# untitled.net
KiCad netlist of a schematic drawn in EAGLE
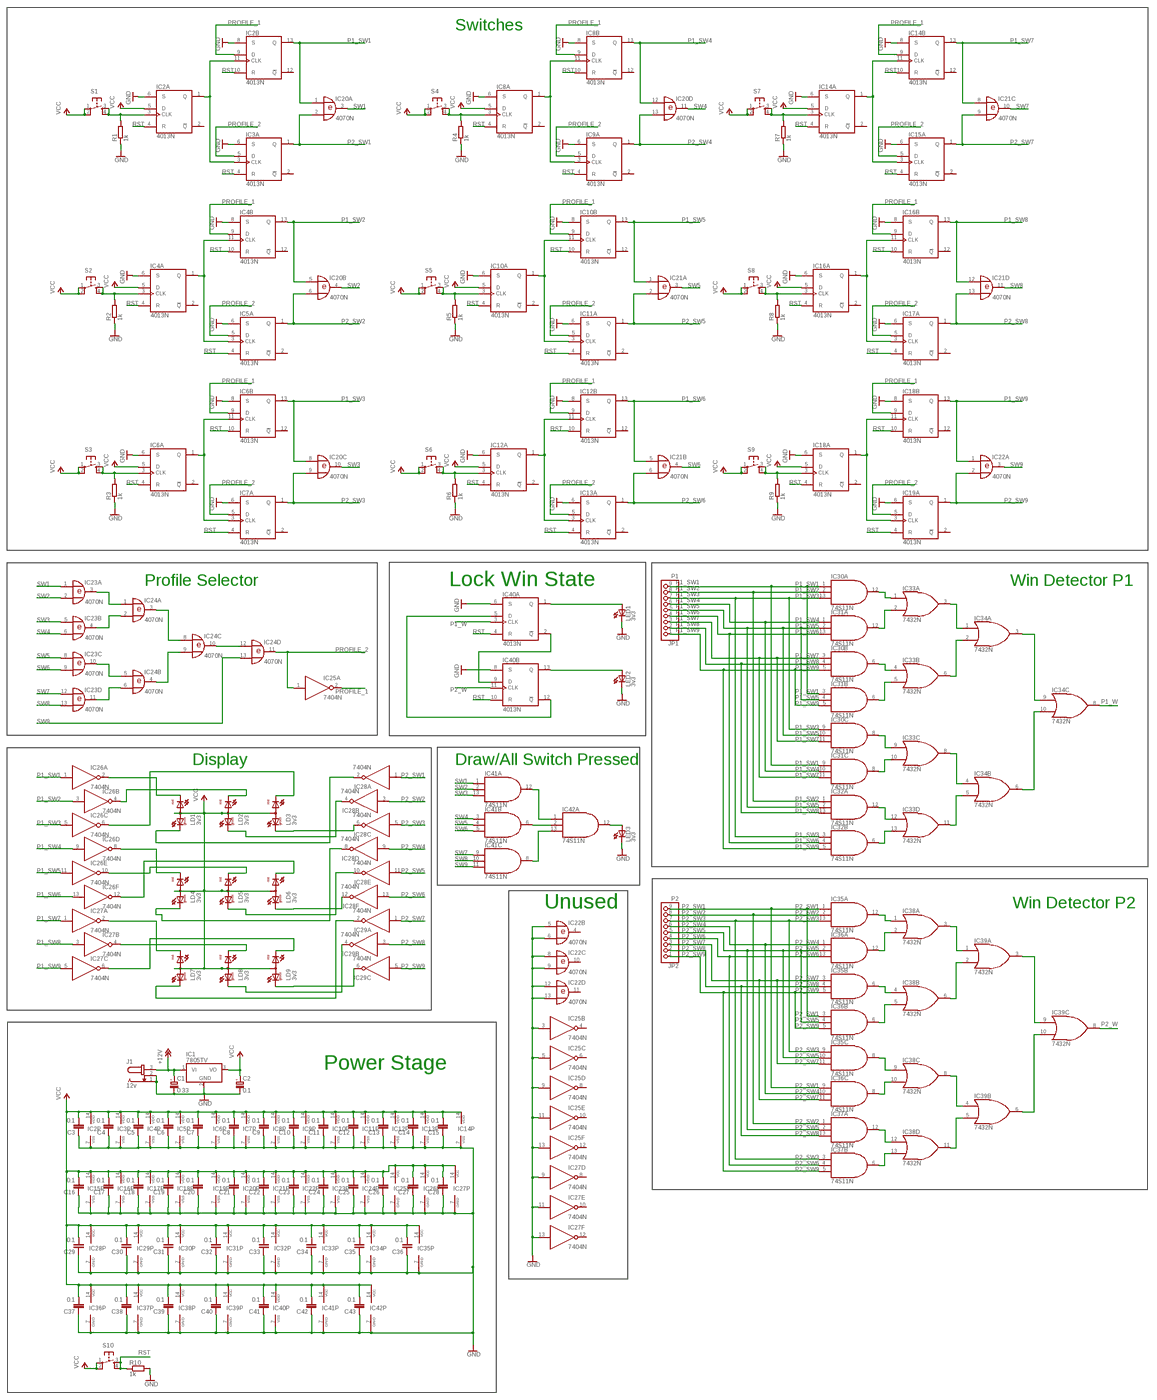
[diagram p0: schematic, sheet 1, overview]
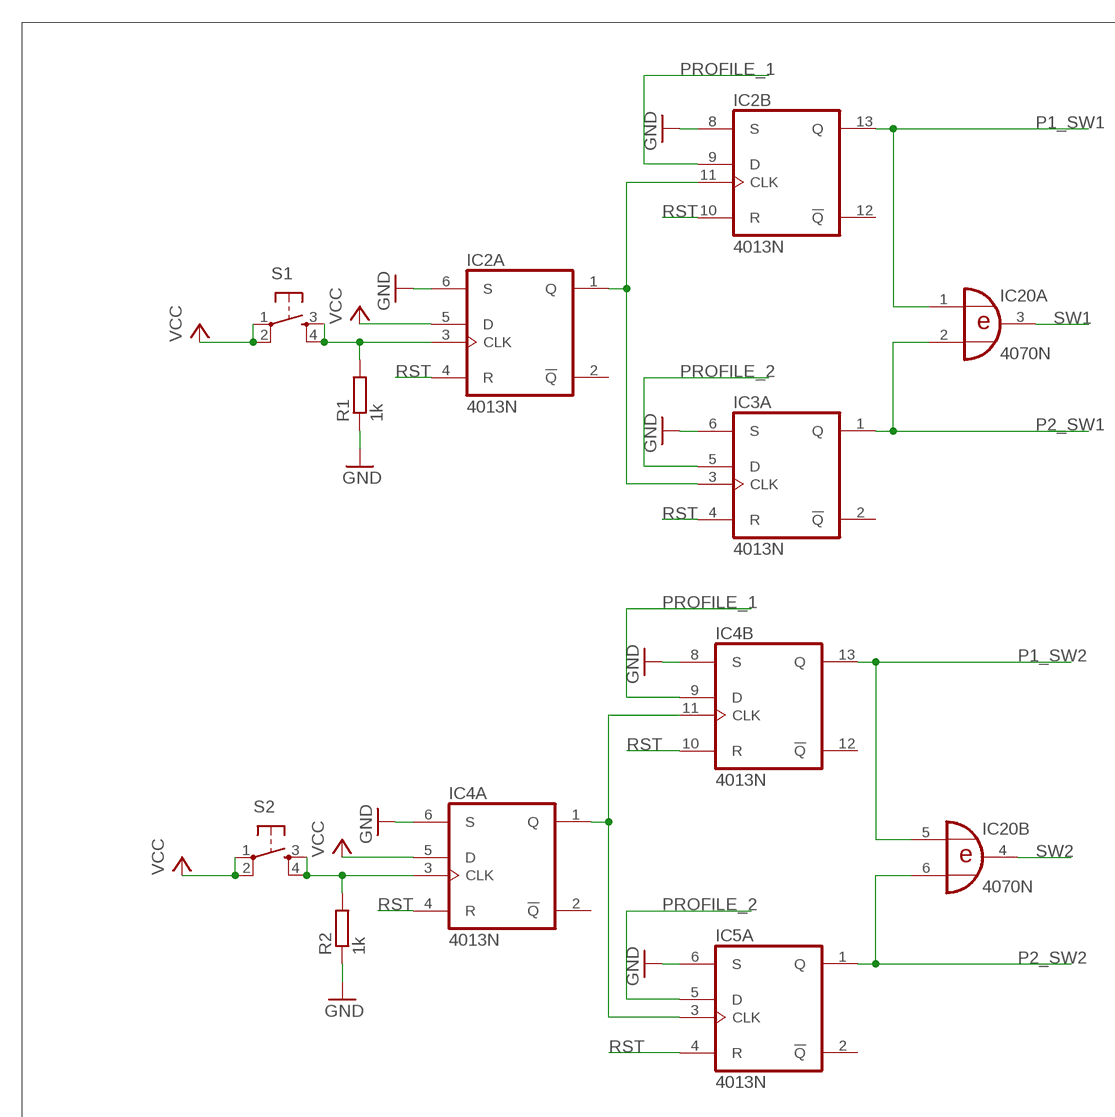
[diagram p1: schematic, sheet 1, part 1 of 4]
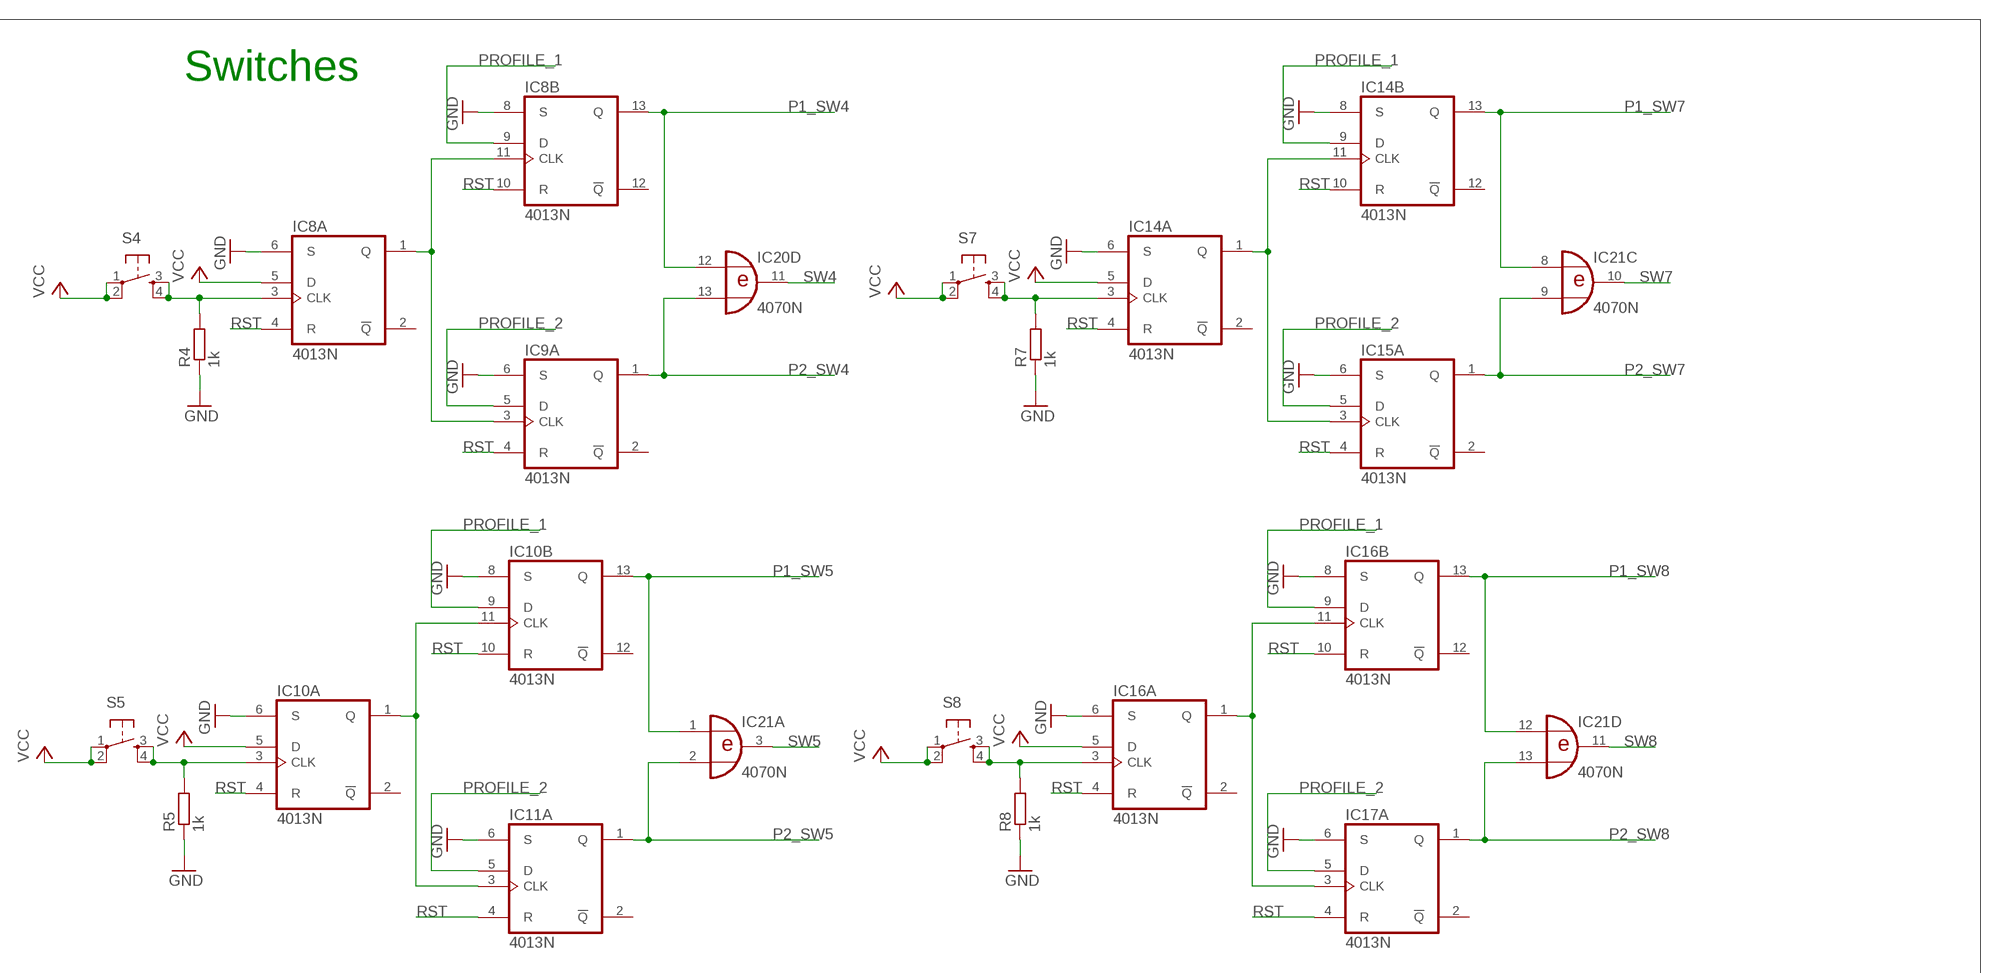
[diagram p2: schematic, sheet 1, part 2 of 4]
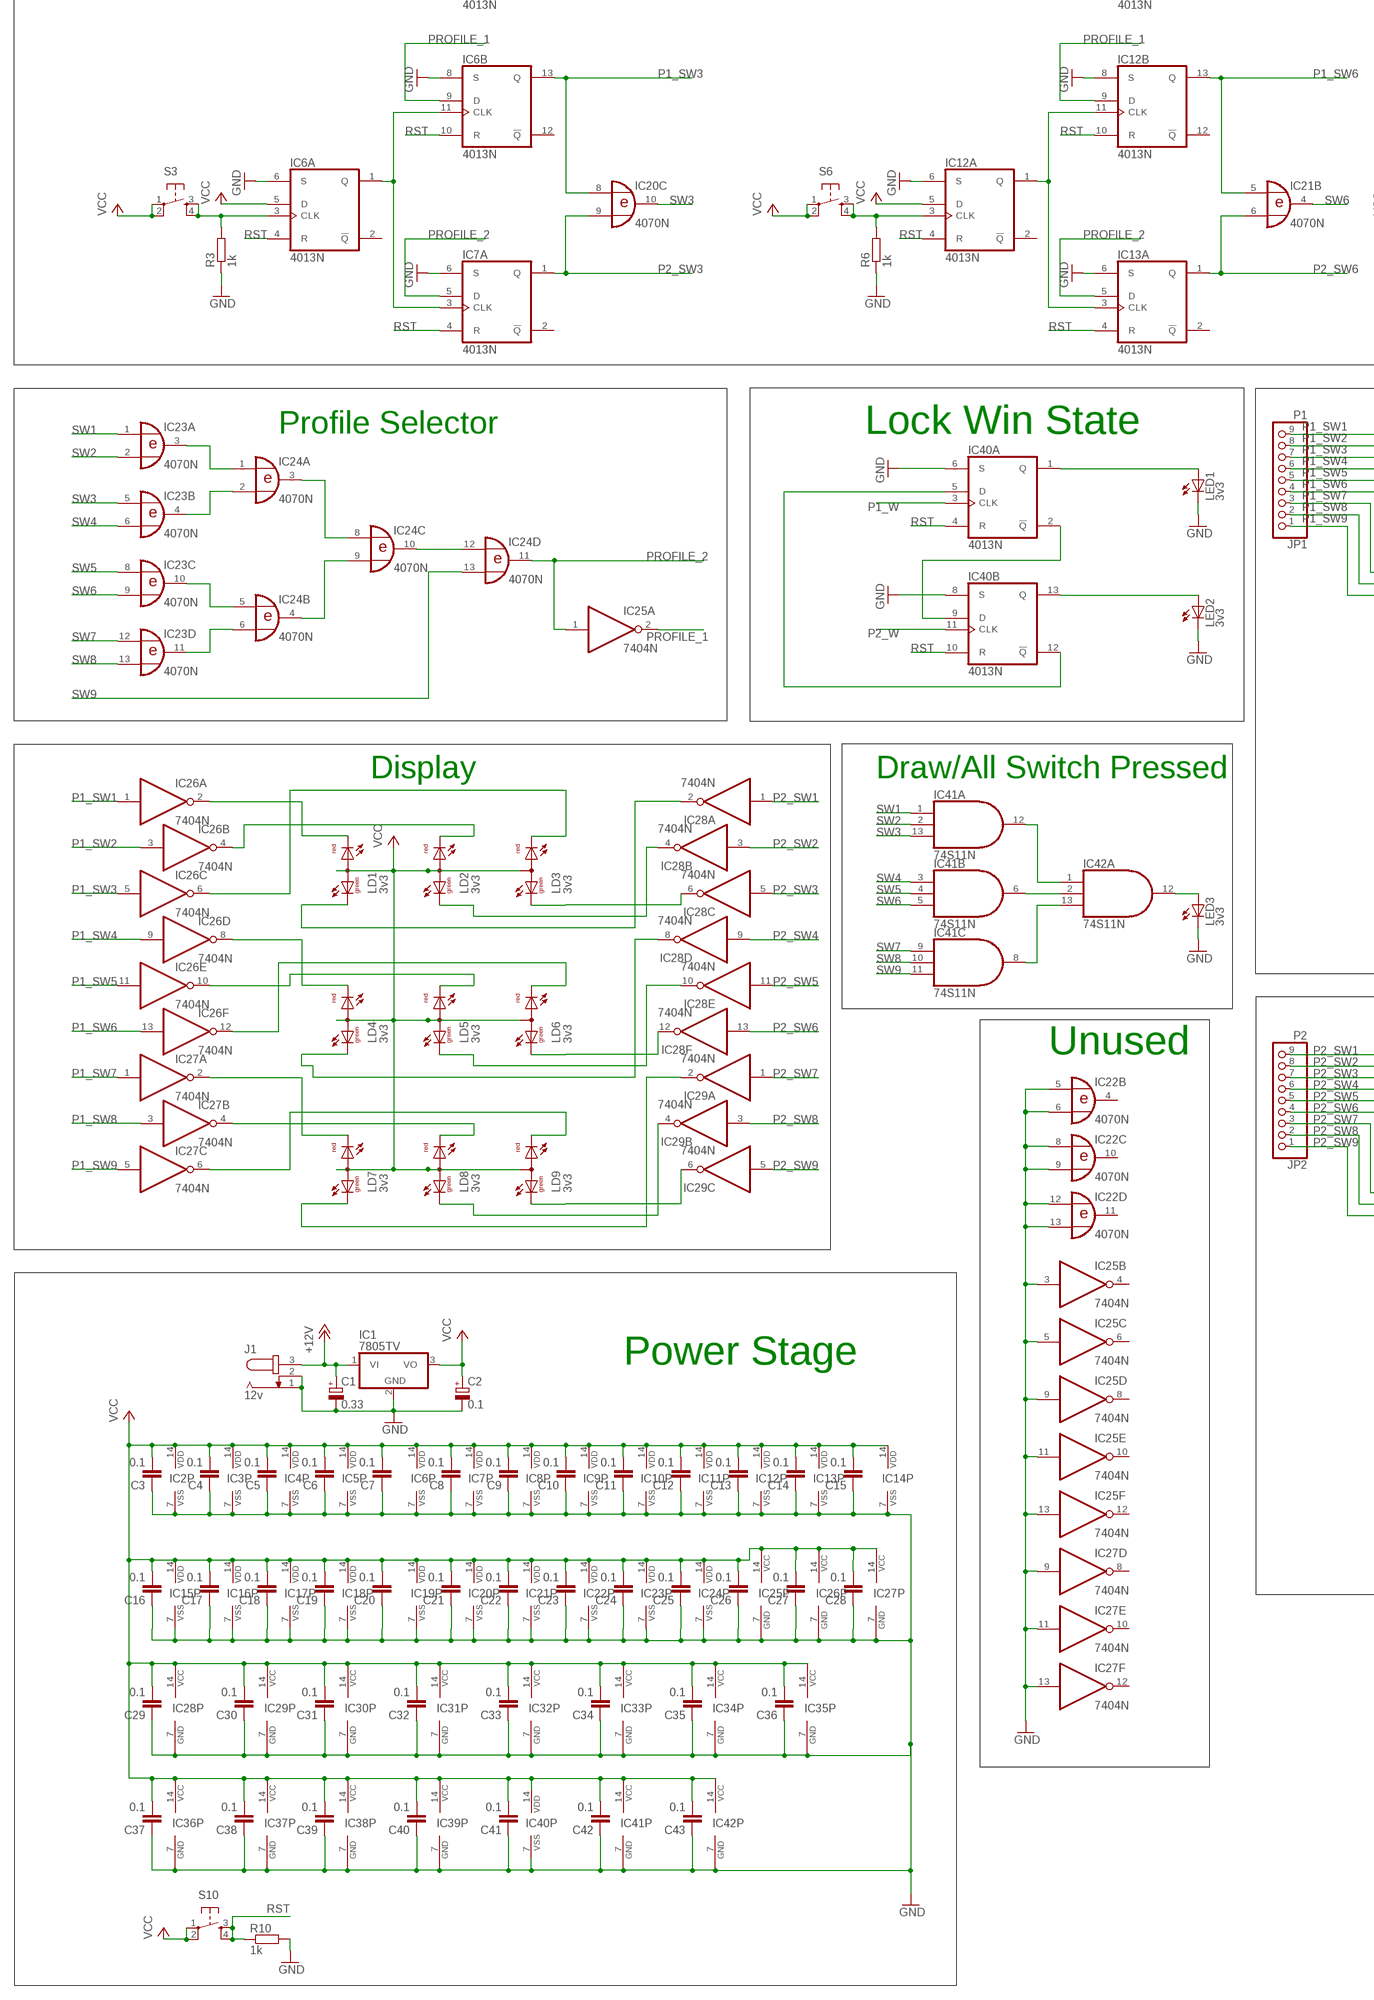
[diagram p3: schematic, sheet 1, part 3 of 4]
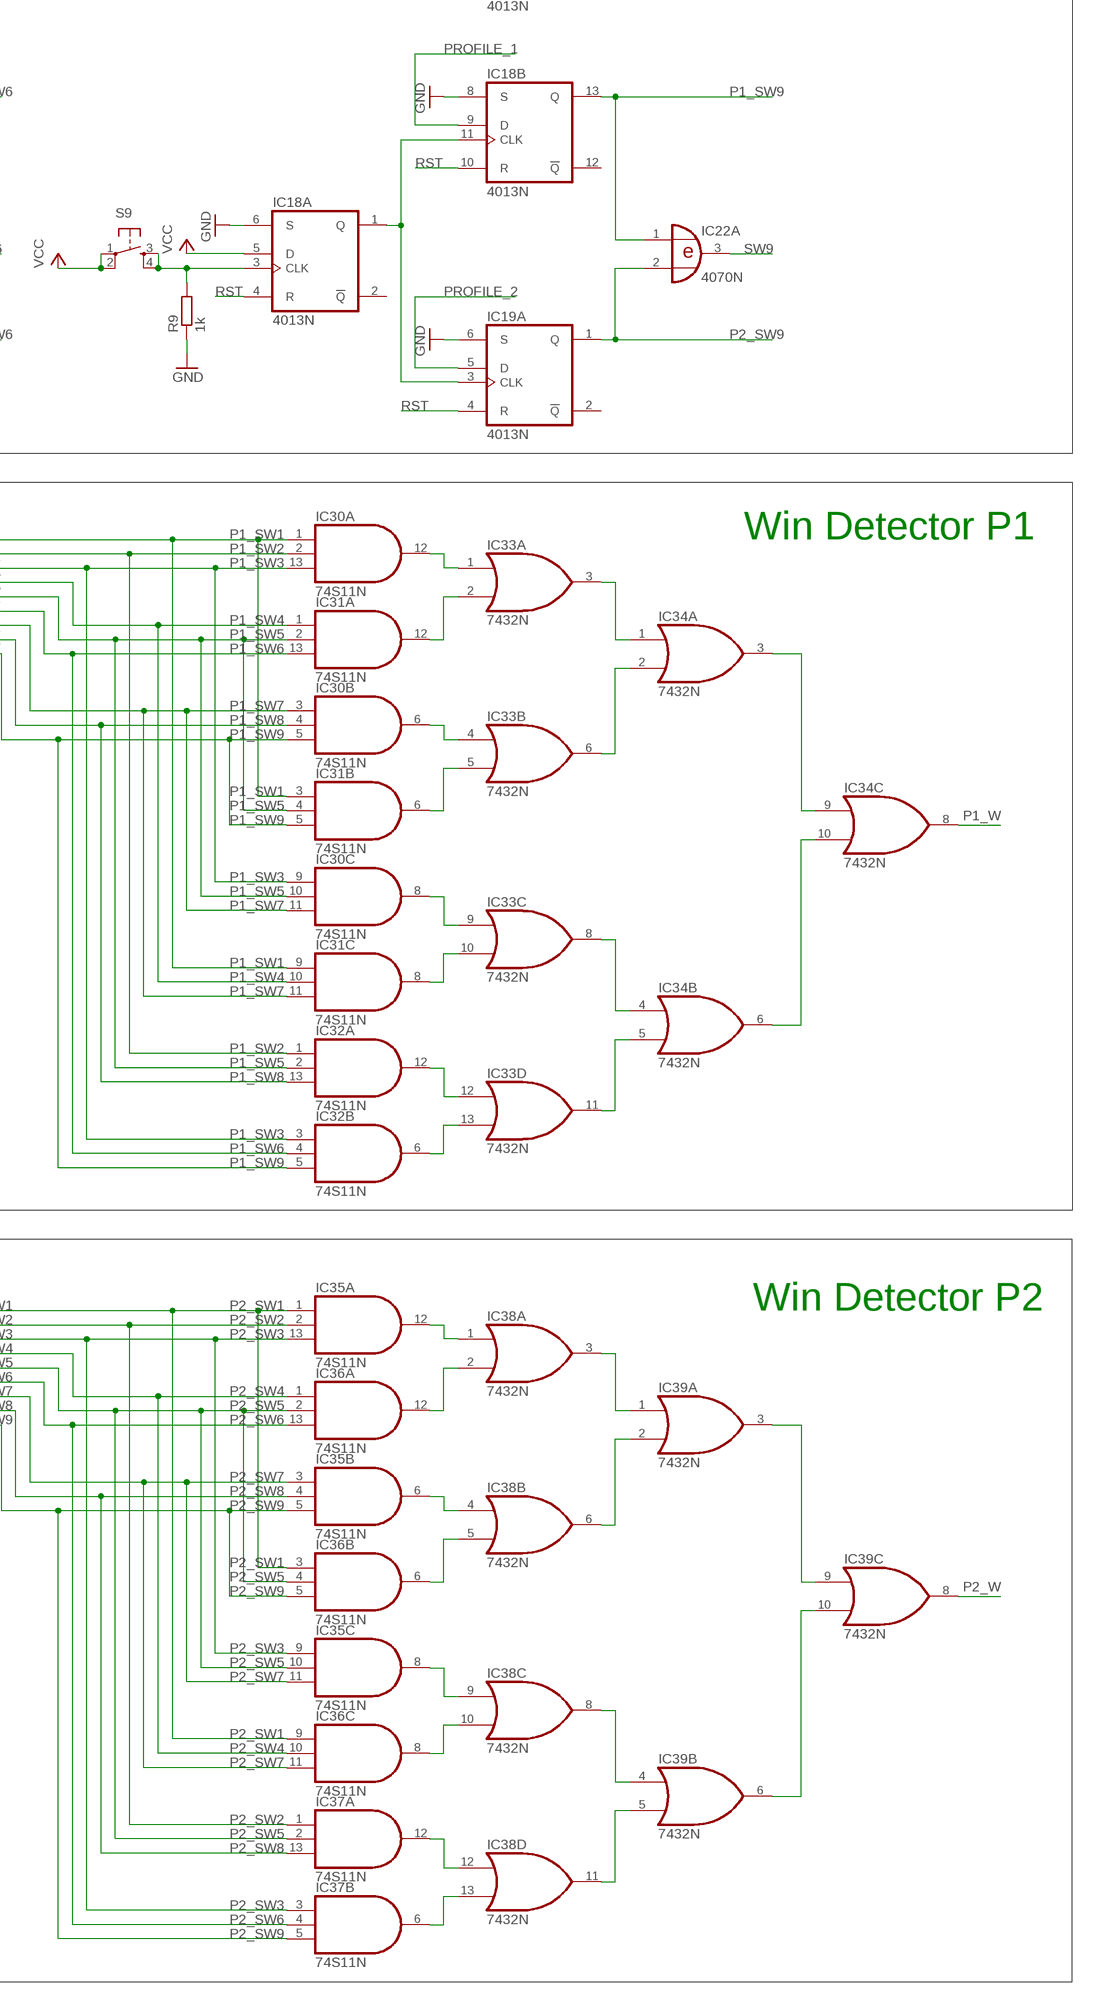
[diagram p4: schematic, sheet 1, part 4 of 4]

(export (version "E")
  (design (tool "Eeschema 10.0.6"))
  (components
    (comp (ref "C1")
      (value "0.33")
      (footprint "eagle-import:E5-8,5")
      (libsource (lib "eagle-import") (part "CPOL-EUE5-8.5"))
    )
    (comp (ref "C2")
      (value "0.1")
      (footprint "eagle-import:E5-8,5")
      (libsource (lib "eagle-import") (part "CPOL-EUE5-8.5"))
    )
    (comp (ref "C3")
      (value "0.1")
      (footprint "eagle-import:C025-050X050")
      (libsource (lib "eagle-import") (part "C-EU025-050X050"))
    )
    (comp (ref "C4")
      (value "0.1")
      (footprint "eagle-import:C025-050X050")
      (libsource (lib "eagle-import") (part "C-EU025-050X050"))
    )
    (comp (ref "C5")
      (value "0.1")
      (footprint "eagle-import:C025-050X050")
      (libsource (lib "eagle-import") (part "C-EU025-050X050"))
    )
    (comp (ref "C6")
      (value "0.1")
      (footprint "eagle-import:C025-050X050")
      (libsource (lib "eagle-import") (part "C-EU025-050X050"))
    )
    (comp (ref "C7")
      (value "0.1")
      (footprint "eagle-import:C025-050X050")
      (libsource (lib "eagle-import") (part "C-EU025-050X050"))
    )
    (comp (ref "C8")
      (value "0.1")
      (footprint "eagle-import:C025-050X050")
      (libsource (lib "eagle-import") (part "C-EU025-050X050"))
    )
    (comp (ref "C9")
      (value "0.1")
      (footprint "eagle-import:C025-050X050")
      (libsource (lib "eagle-import") (part "C-EU025-050X050"))
    )
    (comp (ref "C10")
      (value "0.1")
      (footprint "eagle-import:C025-050X050")
      (libsource (lib "eagle-import") (part "C-EU025-050X050"))
    )
    (comp (ref "C11")
      (value "0.1")
      (footprint "eagle-import:C025-050X050")
      (libsource (lib "eagle-import") (part "C-EU025-050X050"))
    )
    (comp (ref "C12")
      (value "0.1")
      (footprint "eagle-import:C025-050X050")
      (libsource (lib "eagle-import") (part "C-EU025-050X050"))
    )
    (comp (ref "C13")
      (value "0.1")
      (footprint "eagle-import:C025-050X050")
      (libsource (lib "eagle-import") (part "C-EU025-050X050"))
    )
    (comp (ref "C14")
      (value "0.1")
      (footprint "eagle-import:C025-050X050")
      (libsource (lib "eagle-import") (part "C-EU025-050X050"))
    )
    (comp (ref "C15")
      (value "0.1")
      (footprint "eagle-import:C025-050X050")
      (libsource (lib "eagle-import") (part "C-EU025-050X050"))
    )
    (comp (ref "C16")
      (value "0.1")
      (footprint "eagle-import:C025-050X050")
      (libsource (lib "eagle-import") (part "C-EU025-050X050"))
    )
    (comp (ref "C17")
      (value "0.1")
      (footprint "eagle-import:C025-050X050")
      (libsource (lib "eagle-import") (part "C-EU025-050X050"))
    )
    (comp (ref "C18")
      (value "0.1")
      (footprint "eagle-import:C025-050X050")
      (libsource (lib "eagle-import") (part "C-EU025-050X050"))
    )
    (comp (ref "C19")
      (value "0.1")
      (footprint "eagle-import:C025-050X050")
      (libsource (lib "eagle-import") (part "C-EU025-050X050"))
    )
    (comp (ref "C20")
      (value "0.1")
      (footprint "eagle-import:C025-050X050")
      (libsource (lib "eagle-import") (part "C-EU025-050X050"))
    )
    (comp (ref "C21")
      (value "0.1")
      (footprint "eagle-import:C025-050X050")
      (libsource (lib "eagle-import") (part "C-EU025-050X050"))
    )
    (comp (ref "C22")
      (value "0.1")
      (footprint "eagle-import:C025-050X050")
      (libsource (lib "eagle-import") (part "C-EU025-050X050"))
    )
    (comp (ref "C23")
      (value "0.1")
      (footprint "eagle-import:C025-050X050")
      (libsource (lib "eagle-import") (part "C-EU025-050X050"))
    )
    (comp (ref "C24")
      (value "0.1")
      (footprint "eagle-import:C025-050X050")
      (libsource (lib "eagle-import") (part "C-EU025-050X050"))
    )
    (comp (ref "C25")
      (value "0.1")
      (footprint "eagle-import:C025-050X050")
      (libsource (lib "eagle-import") (part "C-EU025-050X050"))
    )
    (comp (ref "C26")
      (value "0.1")
      (footprint "eagle-import:C025-050X050")
      (libsource (lib "eagle-import") (part "C-EU025-050X050"))
    )
    (comp (ref "C27")
      (value "0.1")
      (footprint "eagle-import:C025-050X050")
      (libsource (lib "eagle-import") (part "C-EU025-050X050"))
    )
    (comp (ref "C28")
      (value "0.1")
      (footprint "eagle-import:C025-050X050")
      (libsource (lib "eagle-import") (part "C-EU025-050X050"))
    )
    (comp (ref "C29")
      (value "0.1")
      (footprint "eagle-import:C025-050X050")
      (libsource (lib "eagle-import") (part "C-EU025-050X050"))
    )
    (comp (ref "C30")
      (value "0.1")
      (footprint "eagle-import:C025-050X050")
      (libsource (lib "eagle-import") (part "C-EU025-050X050"))
    )
    (comp (ref "C31")
      (value "0.1")
      (footprint "eagle-import:C025-050X050")
      (libsource (lib "eagle-import") (part "C-EU025-050X050"))
    )
    (comp (ref "C32")
      (value "0.1")
      (footprint "eagle-import:C025-050X050")
      (libsource (lib "eagle-import") (part "C-EU025-050X050"))
    )
    (comp (ref "C33")
      (value "0.1")
      (footprint "eagle-import:C025-050X050")
      (libsource (lib "eagle-import") (part "C-EU025-050X050"))
    )
    (comp (ref "C34")
      (value "0.1")
      (footprint "eagle-import:C025-050X050")
      (libsource (lib "eagle-import") (part "C-EU025-050X050"))
    )
    (comp (ref "C35")
      (value "0.1")
      (footprint "eagle-import:C025-050X050")
      (libsource (lib "eagle-import") (part "C-EU025-050X050"))
    )
    (comp (ref "C36")
      (value "0.1")
      (footprint "eagle-import:C025-050X050")
      (libsource (lib "eagle-import") (part "C-EU025-050X050"))
    )
    (comp (ref "C37")
      (value "0.1")
      (footprint "eagle-import:C025-050X050")
      (libsource (lib "eagle-import") (part "C-EU025-050X050"))
    )
    (comp (ref "C38")
      (value "0.1")
      (footprint "eagle-import:C025-050X050")
      (libsource (lib "eagle-import") (part "C-EU025-050X050"))
    )
    (comp (ref "C39")
      (value "0.1")
      (footprint "eagle-import:C025-050X050")
      (libsource (lib "eagle-import") (part "C-EU025-050X050"))
    )
    (comp (ref "C40")
      (value "0.1")
      (footprint "eagle-import:C025-050X050")
      (libsource (lib "eagle-import") (part "C-EU025-050X050"))
    )
    (comp (ref "C41")
      (value "0.1")
      (footprint "eagle-import:C025-050X050")
      (libsource (lib "eagle-import") (part "C-EU025-050X050"))
    )
    (comp (ref "C42")
      (value "0.1")
      (footprint "eagle-import:C025-050X050")
      (libsource (lib "eagle-import") (part "C-EU025-050X050"))
    )
    (comp (ref "C43")
      (value "0.1")
      (footprint "eagle-import:C025-050X050")
      (libsource (lib "eagle-import") (part "C-EU025-050X050"))
    )
    (comp (ref "IC1")
      (value "7805TV")
      (footprint "eagle-import:TO220V")
      (libsource (lib "eagle-import") (part "78TV05"))
    )
    (comp (ref "IC2")
      (value "4013N")
      (footprint "eagle-import:DIL14")
      (libsource (lib "eagle-import") (part "4013N"))
    )
    (comp (ref "IC3")
      (value "4013N")
      (footprint "eagle-import:DIL14")
      (libsource (lib "eagle-import") (part "4013N"))
    )
    (comp (ref "IC4")
      (value "4013N")
      (footprint "eagle-import:DIL14")
      (libsource (lib "eagle-import") (part "4013N"))
    )
    (comp (ref "IC5")
      (value "4013N")
      (footprint "eagle-import:DIL14")
      (libsource (lib "eagle-import") (part "4013N"))
    )
    (comp (ref "IC6")
      (value "4013N")
      (footprint "eagle-import:DIL14")
      (libsource (lib "eagle-import") (part "4013N"))
    )
    (comp (ref "IC7")
      (value "4013N")
      (footprint "eagle-import:DIL14")
      (libsource (lib "eagle-import") (part "4013N"))
    )
    (comp (ref "IC8")
      (value "4013N")
      (footprint "eagle-import:DIL14")
      (libsource (lib "eagle-import") (part "4013N"))
    )
    (comp (ref "IC9")
      (value "4013N")
      (footprint "eagle-import:DIL14")
      (libsource (lib "eagle-import") (part "4013N"))
    )
    (comp (ref "IC10")
      (value "4013N")
      (footprint "eagle-import:DIL14")
      (libsource (lib "eagle-import") (part "4013N"))
    )
    (comp (ref "IC11")
      (value "4013N")
      (footprint "eagle-import:DIL14")
      (libsource (lib "eagle-import") (part "4013N"))
    )
    (comp (ref "IC12")
      (value "4013N")
      (footprint "eagle-import:DIL14")
      (libsource (lib "eagle-import") (part "4013N"))
    )
    (comp (ref "IC13")
      (value "4013N")
      (footprint "eagle-import:DIL14")
      (libsource (lib "eagle-import") (part "4013N"))
    )
    (comp (ref "IC14")
      (value "4013N")
      (footprint "eagle-import:DIL14")
      (libsource (lib "eagle-import") (part "4013N"))
    )
    (comp (ref "IC15")
      (value "4013N")
      (footprint "eagle-import:DIL14")
      (libsource (lib "eagle-import") (part "4013N"))
    )
    (comp (ref "IC16")
      (value "4013N")
      (footprint "eagle-import:DIL14")
      (libsource (lib "eagle-import") (part "4013N"))
    )
    (comp (ref "IC17")
      (value "4013N")
      (footprint "eagle-import:DIL14")
      (libsource (lib "eagle-import") (part "4013N"))
    )
    (comp (ref "IC18")
      (value "4013N")
      (footprint "eagle-import:DIL14")
      (libsource (lib "eagle-import") (part "4013N"))
    )
    (comp (ref "IC19")
      (value "4013N")
      (footprint "eagle-import:DIL14")
      (libsource (lib "eagle-import") (part "4013N"))
    )
    (comp (ref "IC20")
      (value "4070N")
      (footprint "eagle-import:DIL14")
      (libsource (lib "eagle-import") (part "4070N"))
    )
    (comp (ref "IC21")
      (value "4070N")
      (footprint "eagle-import:DIL14")
      (libsource (lib "eagle-import") (part "4070N"))
    )
    (comp (ref "IC22")
      (value "4070N")
      (footprint "eagle-import:DIL14")
      (libsource (lib "eagle-import") (part "4070N"))
    )
    (comp (ref "IC23")
      (value "4070N")
      (footprint "eagle-import:DIL14")
      (libsource (lib "eagle-import") (part "4070N"))
    )
    (comp (ref "IC24")
      (value "4070N")
      (footprint "eagle-import:DIL14")
      (libsource (lib "eagle-import") (part "4070N"))
    )
    (comp (ref "IC25")
      (value "7404N")
      (footprint "eagle-import:DIL14")
      (libsource (lib "eagle-import") (part "7404N"))
    )
    (comp (ref "IC26")
      (value "7404N")
      (footprint "eagle-import:DIL14")
      (libsource (lib "eagle-import") (part "7404N"))
    )
    (comp (ref "IC27")
      (value "7404N")
      (footprint "eagle-import:DIL14")
      (libsource (lib "eagle-import") (part "7404N"))
    )
    (comp (ref "IC28")
      (value "7404N")
      (footprint "eagle-import:DIL14")
      (libsource (lib "eagle-import") (part "7404N"))
    )
    (comp (ref "IC29")
      (value "7404N")
      (footprint "eagle-import:DIL14")
      (libsource (lib "eagle-import") (part "7404N"))
    )
    (comp (ref "IC30")
      (value "74S11N")
      (footprint "eagle-import:DIL14")
      (libsource (lib "eagle-import") (part "7411NS"))
    )
    (comp (ref "IC31")
      (value "74S11N")
      (footprint "eagle-import:DIL14")
      (libsource (lib "eagle-import") (part "7411NS"))
    )
    (comp (ref "IC32")
      (value "74S11N")
      (footprint "eagle-import:DIL14")
      (libsource (lib "eagle-import") (part "7411NS"))
    )
    (comp (ref "IC33")
      (value "7432N")
      (footprint "eagle-import:DIL14")
      (libsource (lib "eagle-import") (part "7432N"))
    )
    (comp (ref "IC34")
      (value "7432N")
      (footprint "eagle-import:DIL14")
      (libsource (lib "eagle-import") (part "7432N"))
    )
    (comp (ref "IC35")
      (value "74S11N")
      (footprint "eagle-import:DIL14")
      (libsource (lib "eagle-import") (part "7411NS"))
    )
    (comp (ref "IC36")
      (value "74S11N")
      (footprint "eagle-import:DIL14")
      (libsource (lib "eagle-import") (part "7411NS"))
    )
    (comp (ref "IC37")
      (value "74S11N")
      (footprint "eagle-import:DIL14")
      (libsource (lib "eagle-import") (part "7411NS"))
    )
    (comp (ref "IC38")
      (value "7432N")
      (footprint "eagle-import:DIL14")
      (libsource (lib "eagle-import") (part "7432N"))
    )
    (comp (ref "IC39")
      (value "7432N")
      (footprint "eagle-import:DIL14")
      (libsource (lib "eagle-import") (part "7432N"))
    )
    (comp (ref "IC40")
      (value "4013N")
      (footprint "eagle-import:DIL14")
      (libsource (lib "eagle-import") (part "4013N"))
    )
    (comp (ref "IC41")
      (value "74S11N")
      (footprint "eagle-import:DIL14")
      (libsource (lib "eagle-import") (part "7411NS"))
    )
    (comp (ref "IC42")
      (value "74S11N")
      (footprint "eagle-import:DIL14")
      (libsource (lib "eagle-import") (part "7411NS"))
    )
    (comp (ref "J1")
      (value "12v")
      (footprint "eagle-import:SPC4077")
      (libsource (lib "eagle-import") (part "JACK-PLUG0"))
    )
    (comp (ref "JP1")
      (value "P1")
      (footprint "eagle-import:1X09_90")
      (libsource (lib "eagle-import") (part "PINHD-1X9/90"))
    )
    (comp (ref "JP2")
      (value "P2")
      (footprint "eagle-import:1X09_90")
      (libsource (lib "eagle-import") (part "PINHD-1X9/90"))
    )
    (comp (ref "LD1")
      (value "3v3")
      (footprint "eagle-import:DUOLED-A-5MM")
      (libsource (lib "eagle-import") (part "DUOLED-RG-A"))
    )
    (comp (ref "LD2")
      (value "3v3")
      (footprint "eagle-import:DUOLED-A-5MM")
      (libsource (lib "eagle-import") (part "DUOLED-RG-A"))
    )
    (comp (ref "LD3")
      (value "3v3")
      (footprint "eagle-import:DUOLED-A-5MM")
      (libsource (lib "eagle-import") (part "DUOLED-RG-A"))
    )
    (comp (ref "LD4")
      (value "3v3")
      (footprint "eagle-import:DUOLED-A-5MM")
      (libsource (lib "eagle-import") (part "DUOLED-RG-A"))
    )
    (comp (ref "LD5")
      (value "3v3")
      (footprint "eagle-import:DUOLED-A-5MM")
      (libsource (lib "eagle-import") (part "DUOLED-RG-A"))
    )
    (comp (ref "LD6")
      (value "3v3")
      (footprint "eagle-import:DUOLED-A-5MM")
      (libsource (lib "eagle-import") (part "DUOLED-RG-A"))
    )
    (comp (ref "LD7")
      (value "3v3")
      (footprint "eagle-import:DUOLED-A-5MM")
      (libsource (lib "eagle-import") (part "DUOLED-RG-A"))
    )
    (comp (ref "LD8")
      (value "3v3")
      (footprint "eagle-import:DUOLED-A-5MM")
      (libsource (lib "eagle-import") (part "DUOLED-RG-A"))
    )
    (comp (ref "LD9")
      (value "3v3")
      (footprint "eagle-import:DUOLED-A-5MM")
      (libsource (lib "eagle-import") (part "DUOLED-RG-A"))
    )
    (comp (ref "LED1")
      (value "3v3")
      (footprint "eagle-import:LED5MM")
      (libsource (lib "eagle-import") (part "LED5MM"))
    )
    (comp (ref "LED2")
      (value "3v3")
      (footprint "eagle-import:LED5MM")
      (libsource (lib "eagle-import") (part "LED5MM"))
    )
    (comp (ref "LED3")
      (value "3v3")
      (footprint "eagle-import:LED5MM")
      (libsource (lib "eagle-import") (part "LED5MM"))
    )
    (comp (ref "R1")
      (value "1k")
      (footprint "eagle-import:0207_7")
      (libsource (lib "eagle-import") (part "R-EU_0207/7"))
    )
    (comp (ref "R2")
      (value "1k")
      (footprint "eagle-import:0207_7")
      (libsource (lib "eagle-import") (part "R-EU_0207/7"))
    )
    (comp (ref "R3")
      (value "1k")
      (footprint "eagle-import:0207_7")
      (libsource (lib "eagle-import") (part "R-EU_0207/7"))
    )
    (comp (ref "R4")
      (value "1k")
      (footprint "eagle-import:0207_7")
      (libsource (lib "eagle-import") (part "R-EU_0207/7"))
    )
    (comp (ref "R5")
      (value "1k")
      (footprint "eagle-import:0207_7")
      (libsource (lib "eagle-import") (part "R-EU_0207/7"))
    )
    (comp (ref "R6")
      (value "1k")
      (footprint "eagle-import:0207_7")
      (libsource (lib "eagle-import") (part "R-EU_0207/7"))
    )
    (comp (ref "R7")
      (value "1k")
      (footprint "eagle-import:0207_7")
      (libsource (lib "eagle-import") (part "R-EU_0207/7"))
    )
    (comp (ref "R8")
      (value "1k")
      (footprint "eagle-import:0207_7")
      (libsource (lib "eagle-import") (part "R-EU_0207/7"))
    )
    (comp (ref "R9")
      (value "1k")
      (footprint "eagle-import:0207_7")
      (libsource (lib "eagle-import") (part "R-EU_0207/7"))
    )
    (comp (ref "R10")
      (value "1k")
      (footprint "eagle-import:0207_7")
      (libsource (lib "eagle-import") (part "R-EU_0207/7"))
    )
    (comp (ref "S1")
      (value "TAC_SWITCHPTH")
      (footprint "eagle-import:TACTILE-PTH")
      (libsource (lib "eagle-import") (part "TAC_SWITCHPTH"))
    )
    (comp (ref "S2")
      (value "TAC_SWITCHPTH")
      (footprint "eagle-import:TACTILE-PTH")
      (libsource (lib "eagle-import") (part "TAC_SWITCHPTH"))
    )
    (comp (ref "S3")
      (value "TAC_SWITCHPTH")
      (footprint "eagle-import:TACTILE-PTH")
      (libsource (lib "eagle-import") (part "TAC_SWITCHPTH"))
    )
    (comp (ref "S4")
      (value "TAC_SWITCHPTH")
      (footprint "eagle-import:TACTILE-PTH")
      (libsource (lib "eagle-import") (part "TAC_SWITCHPTH"))
    )
    (comp (ref "S5")
      (value "TAC_SWITCHPTH")
      (footprint "eagle-import:TACTILE-PTH")
      (libsource (lib "eagle-import") (part "TAC_SWITCHPTH"))
    )
    (comp (ref "S6")
      (value "TAC_SWITCHPTH")
      (footprint "eagle-import:TACTILE-PTH")
      (libsource (lib "eagle-import") (part "TAC_SWITCHPTH"))
    )
    (comp (ref "S7")
      (value "TAC_SWITCHPTH")
      (footprint "eagle-import:TACTILE-PTH")
      (libsource (lib "eagle-import") (part "TAC_SWITCHPTH"))
    )
    (comp (ref "S8")
      (value "TAC_SWITCHPTH")
      (footprint "eagle-import:TACTILE-PTH")
      (libsource (lib "eagle-import") (part "TAC_SWITCHPTH"))
    )
    (comp (ref "S9")
      (value "TAC_SWITCHPTH")
      (footprint "eagle-import:TACTILE-PTH")
      (libsource (lib "eagle-import") (part "TAC_SWITCHPTH"))
    )
    (comp (ref "S10")
      (value "TAC_SWITCHPTH")
      (footprint "eagle-import:TACTILE-PTH")
      (libsource (lib "eagle-import") (part "TAC_SWITCHPTH"))
    )
  )
  (nets
    (net (code "1") (name "+12V") (class "Default")
      (node (ref "C1") (pin "+") (pinfunction "+_+") (pintype "passive"))
      (node (ref "IC1") (pin "1") (pinfunction "VI_1") (pintype "input"))
      (node (ref "J1") (pin "3") (pinfunction "3_3") (pintype "passive"))
    )
    (net (code "2") (name "/P1_SW1") (class "Default")
      (node (ref "IC2") (pin "13") (pinfunction "Q_13") (pintype "output"))
      (node (ref "IC20") (pin "1") (pinfunction "I0_1") (pintype "input"))
      (node (ref "IC26") (pin "1") (pinfunction "I_1") (pintype "input"))
      (node (ref "IC30") (pin "1") (pinfunction "I0_1") (pintype "input"))
      (node (ref "IC31") (pin "3") (pinfunction "I0_3") (pintype "input"))
      (node (ref "IC31") (pin "9") (pinfunction "I0_9") (pintype "input"))
      (node (ref "JP1") (pin "9") (pinfunction "9_9") (pintype "passive"))
    )
    (net (code "3") (name "/P1_SW2") (class "Default")
      (node (ref "IC20") (pin "5") (pinfunction "I0_5") (pintype "input"))
      (node (ref "IC26") (pin "3") (pinfunction "I_3") (pintype "input"))
      (node (ref "IC30") (pin "2") (pinfunction "I1_2") (pintype "input"))
      (node (ref "IC32") (pin "1") (pinfunction "I0_1") (pintype "input"))
      (node (ref "IC4") (pin "13") (pinfunction "Q_13") (pintype "output"))
      (node (ref "JP1") (pin "8") (pinfunction "8_8") (pintype "passive"))
    )
    (net (code "4") (name "/P1_SW3") (class "Default")
      (node (ref "IC20") (pin "8") (pinfunction "I0_8") (pintype "input"))
      (node (ref "IC26") (pin "5") (pinfunction "I_5") (pintype "input"))
      (node (ref "IC30") (pin "13") (pinfunction "I2_13") (pintype "input"))
      (node (ref "IC30") (pin "9") (pinfunction "I0_9") (pintype "input"))
      (node (ref "IC32") (pin "3") (pinfunction "I0_3") (pintype "input"))
      (node (ref "IC6") (pin "13") (pinfunction "Q_13") (pintype "output"))
      (node (ref "JP1") (pin "7") (pinfunction "7_7") (pintype "passive"))
    )
    (net (code "5") (name "/P1_SW4") (class "Default")
      (node (ref "IC20") (pin "12") (pinfunction "I0_12") (pintype "input"))
      (node (ref "IC26") (pin "9") (pinfunction "I_9") (pintype "input"))
      (node (ref "IC31") (pin "1") (pinfunction "I0_1") (pintype "input"))
      (node (ref "IC31") (pin "10") (pinfunction "I1_10") (pintype "input"))
      (node (ref "IC8") (pin "13") (pinfunction "Q_13") (pintype "output"))
      (node (ref "JP1") (pin "6") (pinfunction "6_6") (pintype "passive"))
    )
    (net (code "6") (name "/P1_SW5") (class "Default")
      (node (ref "IC10") (pin "13") (pinfunction "Q_13") (pintype "output"))
      (node (ref "IC21") (pin "1") (pinfunction "I0_1") (pintype "input"))
      (node (ref "IC26") (pin "11") (pinfunction "I_11") (pintype "input"))
      (node (ref "IC30") (pin "10") (pinfunction "I1_10") (pintype "input"))
      (node (ref "IC31") (pin "2") (pinfunction "I1_2") (pintype "input"))
      (node (ref "IC31") (pin "4") (pinfunction "I1_4") (pintype "input"))
      (node (ref "IC32") (pin "2") (pinfunction "I1_2") (pintype "input"))
      (node (ref "JP1") (pin "5") (pinfunction "5_5") (pintype "passive"))
    )
    (net (code "7") (name "/P1_SW6") (class "Default")
      (node (ref "IC12") (pin "13") (pinfunction "Q_13") (pintype "output"))
      (node (ref "IC21") (pin "5") (pinfunction "I0_5") (pintype "input"))
      (node (ref "IC26") (pin "13") (pinfunction "I_13") (pintype "input"))
      (node (ref "IC31") (pin "13") (pinfunction "I2_13") (pintype "input"))
      (node (ref "IC32") (pin "4") (pinfunction "I1_4") (pintype "input"))
      (node (ref "JP1") (pin "4") (pinfunction "4_4") (pintype "passive"))
    )
    (net (code "8") (name "/P1_SW7") (class "Default")
      (node (ref "IC14") (pin "13") (pinfunction "Q_13") (pintype "output"))
      (node (ref "IC21") (pin "8") (pinfunction "I0_8") (pintype "input"))
      (node (ref "IC27") (pin "1") (pinfunction "I_1") (pintype "input"))
      (node (ref "IC30") (pin "11") (pinfunction "I2_11") (pintype "input"))
      (node (ref "IC30") (pin "3") (pinfunction "I0_3") (pintype "input"))
      (node (ref "IC31") (pin "11") (pinfunction "I2_11") (pintype "input"))
      (node (ref "JP1") (pin "3") (pinfunction "3_3") (pintype "passive"))
    )
    (net (code "9") (name "/P1_SW8") (class "Default")
      (node (ref "IC16") (pin "13") (pinfunction "Q_13") (pintype "output"))
      (node (ref "IC21") (pin "12") (pinfunction "I0_12") (pintype "input"))
      (node (ref "IC27") (pin "3") (pinfunction "I_3") (pintype "input"))
      (node (ref "IC30") (pin "4") (pinfunction "I1_4") (pintype "input"))
      (node (ref "IC32") (pin "13") (pinfunction "I2_13") (pintype "input"))
      (node (ref "JP1") (pin "2") (pinfunction "2_2") (pintype "passive"))
    )
    (net (code "10") (name "/P1_SW9") (class "Default")
      (node (ref "IC18") (pin "13") (pinfunction "Q_13") (pintype "output"))
      (node (ref "IC22") (pin "1") (pinfunction "I0_1") (pintype "input"))
      (node (ref "IC27") (pin "5") (pinfunction "I_5") (pintype "input"))
      (node (ref "IC30") (pin "5") (pinfunction "I2_5") (pintype "input"))
      (node (ref "IC31") (pin "5") (pinfunction "I2_5") (pintype "input"))
      (node (ref "IC32") (pin "5") (pinfunction "I2_5") (pintype "input"))
      (node (ref "JP1") (pin "1") (pinfunction "1_1") (pintype "passive"))
    )
    (net (code "11") (name "/P1_W") (class "Default")
      (node (ref "IC34") (pin "8") (pinfunction "O_8") (pintype "output"))
      (node (ref "IC40") (pin "3") (pinfunction "CLK_3") (pintype "input"))
    )
    (net (code "12") (name "/P2_SW1") (class "Default")
      (node (ref "IC20") (pin "2") (pinfunction "I1_2") (pintype "input"))
      (node (ref "IC28") (pin "1") (pinfunction "I_1") (pintype "input"))
      (node (ref "IC3") (pin "1") (pinfunction "Q_1") (pintype "output"))
      (node (ref "IC35") (pin "1") (pinfunction "I0_1") (pintype "input"))
      (node (ref "IC36") (pin "3") (pinfunction "I0_3") (pintype "input"))
      (node (ref "IC36") (pin "9") (pinfunction "I0_9") (pintype "input"))
      (node (ref "JP2") (pin "9") (pinfunction "9_9") (pintype "passive"))
    )
    (net (code "13") (name "/P2_SW2") (class "Default")
      (node (ref "IC20") (pin "6") (pinfunction "I1_6") (pintype "input"))
      (node (ref "IC28") (pin "3") (pinfunction "I_3") (pintype "input"))
      (node (ref "IC35") (pin "2") (pinfunction "I1_2") (pintype "input"))
      (node (ref "IC37") (pin "1") (pinfunction "I0_1") (pintype "input"))
      (node (ref "IC5") (pin "1") (pinfunction "Q_1") (pintype "output"))
      (node (ref "JP2") (pin "8") (pinfunction "8_8") (pintype "passive"))
    )
    (net (code "14") (name "/P2_SW3") (class "Default")
      (node (ref "IC20") (pin "9") (pinfunction "I1_9") (pintype "input"))
      (node (ref "IC28") (pin "5") (pinfunction "I_5") (pintype "input"))
      (node (ref "IC35") (pin "13") (pinfunction "I2_13") (pintype "input"))
      (node (ref "IC35") (pin "9") (pinfunction "I0_9") (pintype "input"))
      (node (ref "IC37") (pin "3") (pinfunction "I0_3") (pintype "input"))
      (node (ref "IC7") (pin "1") (pinfunction "Q_1") (pintype "output"))
      (node (ref "JP2") (pin "7") (pinfunction "7_7") (pintype "passive"))
    )
    (net (code "15") (name "/P2_SW4") (class "Default")
      (node (ref "IC20") (pin "13") (pinfunction "I1_13") (pintype "input"))
      (node (ref "IC28") (pin "9") (pinfunction "I_9") (pintype "input"))
      (node (ref "IC36") (pin "1") (pinfunction "I0_1") (pintype "input"))
      (node (ref "IC36") (pin "10") (pinfunction "I1_10") (pintype "input"))
      (node (ref "IC9") (pin "1") (pinfunction "Q_1") (pintype "output"))
      (node (ref "JP2") (pin "6") (pinfunction "6_6") (pintype "passive"))
    )
    (net (code "16") (name "/P2_SW5") (class "Default")
      (node (ref "IC11") (pin "1") (pinfunction "Q_1") (pintype "output"))
      (node (ref "IC21") (pin "2") (pinfunction "I1_2") (pintype "input"))
      (node (ref "IC28") (pin "11") (pinfunction "I_11") (pintype "input"))
      (node (ref "IC35") (pin "10") (pinfunction "I1_10") (pintype "input"))
      (node (ref "IC36") (pin "2") (pinfunction "I1_2") (pintype "input"))
      (node (ref "IC36") (pin "4") (pinfunction "I1_4") (pintype "input"))
      (node (ref "IC37") (pin "2") (pinfunction "I1_2") (pintype "input"))
      (node (ref "JP2") (pin "5") (pinfunction "5_5") (pintype "passive"))
    )
    (net (code "17") (name "/P2_SW6") (class "Default")
      (node (ref "IC13") (pin "1") (pinfunction "Q_1") (pintype "output"))
      (node (ref "IC21") (pin "6") (pinfunction "I1_6") (pintype "input"))
      (node (ref "IC28") (pin "13") (pinfunction "I_13") (pintype "input"))
      (node (ref "IC36") (pin "13") (pinfunction "I2_13") (pintype "input"))
      (node (ref "IC37") (pin "4") (pinfunction "I1_4") (pintype "input"))
      (node (ref "JP2") (pin "4") (pinfunction "4_4") (pintype "passive"))
    )
    (net (code "18") (name "/P2_SW7") (class "Default")
      (node (ref "IC15") (pin "1") (pinfunction "Q_1") (pintype "output"))
      (node (ref "IC21") (pin "9") (pinfunction "I1_9") (pintype "input"))
      (node (ref "IC29") (pin "1") (pinfunction "I_1") (pintype "input"))
      (node (ref "IC35") (pin "11") (pinfunction "I2_11") (pintype "input"))
      (node (ref "IC35") (pin "3") (pinfunction "I0_3") (pintype "input"))
      (node (ref "IC36") (pin "11") (pinfunction "I2_11") (pintype "input"))
      (node (ref "JP2") (pin "3") (pinfunction "3_3") (pintype "passive"))
    )
    (net (code "19") (name "/P2_SW8") (class "Default")
      (node (ref "IC17") (pin "1") (pinfunction "Q_1") (pintype "output"))
      (node (ref "IC21") (pin "13") (pinfunction "I1_13") (pintype "input"))
      (node (ref "IC29") (pin "3") (pinfunction "I_3") (pintype "input"))
      (node (ref "IC35") (pin "4") (pinfunction "I1_4") (pintype "input"))
      (node (ref "IC37") (pin "13") (pinfunction "I2_13") (pintype "input"))
      (node (ref "JP2") (pin "2") (pinfunction "2_2") (pintype "passive"))
    )
    (net (code "20") (name "/P2_SW9") (class "Default")
      (node (ref "IC19") (pin "1") (pinfunction "Q_1") (pintype "output"))
      (node (ref "IC22") (pin "2") (pinfunction "I1_2") (pintype "input"))
      (node (ref "IC29") (pin "5") (pinfunction "I_5") (pintype "input"))
      (node (ref "IC35") (pin "5") (pinfunction "I2_5") (pintype "input"))
      (node (ref "IC36") (pin "5") (pinfunction "I2_5") (pintype "input"))
      (node (ref "IC37") (pin "5") (pinfunction "I2_5") (pintype "input"))
      (node (ref "JP2") (pin "1") (pinfunction "1_1") (pintype "passive"))
    )
    (net (code "21") (name "/P2_W") (class "Default")
      (node (ref "IC39") (pin "8") (pinfunction "O_8") (pintype "output"))
      (node (ref "IC40") (pin "11") (pinfunction "CLK_11") (pintype "input"))
    )
    (net (code "22") (name "/PROFILE_1") (class "Default")
      (node (ref "IC10") (pin "9") (pinfunction "D_9") (pintype "input"))
      (node (ref "IC12") (pin "9") (pinfunction "D_9") (pintype "input"))
      (node (ref "IC14") (pin "9") (pinfunction "D_9") (pintype "input"))
      (node (ref "IC16") (pin "9") (pinfunction "D_9") (pintype "input"))
      (node (ref "IC18") (pin "9") (pinfunction "D_9") (pintype "input"))
      (node (ref "IC2") (pin "9") (pinfunction "D_9") (pintype "input"))
      (node (ref "IC25") (pin "2") (pinfunction "O_2") (pintype "output"))
      (node (ref "IC4") (pin "9") (pinfunction "D_9") (pintype "input"))
      (node (ref "IC6") (pin "9") (pinfunction "D_9") (pintype "input"))
      (node (ref "IC8") (pin "9") (pinfunction "D_9") (pintype "input"))
    )
    (net (code "23") (name "/PROFILE_2") (class "Default")
      (node (ref "IC11") (pin "5") (pinfunction "D_5") (pintype "input"))
      (node (ref "IC13") (pin "5") (pinfunction "D_5") (pintype "input"))
      (node (ref "IC15") (pin "5") (pinfunction "D_5") (pintype "input"))
      (node (ref "IC17") (pin "5") (pinfunction "D_5") (pintype "input"))
      (node (ref "IC19") (pin "5") (pinfunction "D_5") (pintype "input"))
      (node (ref "IC24") (pin "11") (pinfunction "O_11") (pintype "output"))
      (node (ref "IC25") (pin "1") (pinfunction "I_1") (pintype "input"))
      (node (ref "IC3") (pin "5") (pinfunction "D_5") (pintype "input"))
      (node (ref "IC5") (pin "5") (pinfunction "D_5") (pintype "input"))
      (node (ref "IC7") (pin "5") (pinfunction "D_5") (pintype "input"))
      (node (ref "IC9") (pin "5") (pinfunction "D_5") (pintype "input"))
    )
    (net (code "24") (name "/RST") (class "Default")
      (node (ref "IC10") (pin "10") (pinfunction "R_10") (pintype "input"))
      (node (ref "IC10") (pin "4") (pinfunction "R_4") (pintype "input"))
      (node (ref "IC11") (pin "4") (pinfunction "R_4") (pintype "input"))
      (node (ref "IC12") (pin "10") (pinfunction "R_10") (pintype "input"))
      (node (ref "IC12") (pin "4") (pinfunction "R_4") (pintype "input"))
      (node (ref "IC13") (pin "4") (pinfunction "R_4") (pintype "input"))
      (node (ref "IC14") (pin "10") (pinfunction "R_10") (pintype "input"))
      (node (ref "IC14") (pin "4") (pinfunction "R_4") (pintype "input"))
      (node (ref "IC15") (pin "4") (pinfunction "R_4") (pintype "input"))
      (node (ref "IC16") (pin "10") (pinfunction "R_10") (pintype "input"))
      (node (ref "IC16") (pin "4") (pinfunction "R_4") (pintype "input"))
      (node (ref "IC17") (pin "4") (pinfunction "R_4") (pintype "input"))
      (node (ref "IC18") (pin "10") (pinfunction "R_10") (pintype "input"))
      (node (ref "IC18") (pin "4") (pinfunction "R_4") (pintype "input"))
      (node (ref "IC19") (pin "4") (pinfunction "R_4") (pintype "input"))
      (node (ref "IC2") (pin "10") (pinfunction "R_10") (pintype "input"))
      (node (ref "IC2") (pin "4") (pinfunction "R_4") (pintype "input"))
      (node (ref "IC3") (pin "4") (pinfunction "R_4") (pintype "input"))
      (node (ref "IC4") (pin "10") (pinfunction "R_10") (pintype "input"))
      (node (ref "IC4") (pin "4") (pinfunction "R_4") (pintype "input"))
      (node (ref "IC40") (pin "10") (pinfunction "R_10") (pintype "input"))
      (node (ref "IC40") (pin "4") (pinfunction "R_4") (pintype "input"))
      (node (ref "IC5") (pin "4") (pinfunction "R_4") (pintype "input"))
      (node (ref "IC6") (pin "10") (pinfunction "R_10") (pintype "input"))
      (node (ref "IC6") (pin "4") (pinfunction "R_4") (pintype "input"))
      (node (ref "IC7") (pin "4") (pinfunction "R_4") (pintype "input"))
      (node (ref "IC8") (pin "10") (pinfunction "R_10") (pintype "input"))
      (node (ref "IC8") (pin "4") (pinfunction "R_4") (pintype "input"))
      (node (ref "IC9") (pin "4") (pinfunction "R_4") (pintype "input"))
      (node (ref "R10") (pin "1") (pinfunction "1_1") (pintype "passive"))
      (node (ref "S10") (pin "3") (pinfunction "3_3") (pintype "passive"))
      (node (ref "S10") (pin "4") (pinfunction "4_4") (pintype "passive"))
    )
    (net (code "25") (name "/SW1") (class "Default")
      (node (ref "IC20") (pin "3") (pinfunction "O_3") (pintype "output"))
      (node (ref "IC23") (pin "1") (pinfunction "I0_1") (pintype "input"))
      (node (ref "IC41") (pin "1") (pinfunction "I0_1") (pintype "input"))
    )
    (net (code "26") (name "/SW2") (class "Default")
      (node (ref "IC20") (pin "4") (pinfunction "O_4") (pintype "output"))
      (node (ref "IC23") (pin "2") (pinfunction "I1_2") (pintype "input"))
      (node (ref "IC41") (pin "2") (pinfunction "I1_2") (pintype "input"))
    )
    (net (code "27") (name "/SW3") (class "Default")
      (node (ref "IC20") (pin "10") (pinfunction "O_10") (pintype "output"))
      (node (ref "IC23") (pin "5") (pinfunction "I0_5") (pintype "input"))
      (node (ref "IC41") (pin "13") (pinfunction "I2_13") (pintype "input"))
    )
    (net (code "28") (name "/SW4") (class "Default")
      (node (ref "IC20") (pin "11") (pinfunction "O_11") (pintype "output"))
      (node (ref "IC23") (pin "6") (pinfunction "I1_6") (pintype "input"))
      (node (ref "IC41") (pin "3") (pinfunction "I0_3") (pintype "input"))
    )
    (net (code "29") (name "/SW5") (class "Default")
      (node (ref "IC21") (pin "3") (pinfunction "O_3") (pintype "output"))
      (node (ref "IC23") (pin "8") (pinfunction "I0_8") (pintype "input"))
      (node (ref "IC41") (pin "4") (pinfunction "I1_4") (pintype "input"))
    )
    (net (code "30") (name "/SW6") (class "Default")
      (node (ref "IC21") (pin "4") (pinfunction "O_4") (pintype "output"))
      (node (ref "IC23") (pin "9") (pinfunction "I1_9") (pintype "input"))
      (node (ref "IC41") (pin "5") (pinfunction "I2_5") (pintype "input"))
    )
    (net (code "31") (name "/SW7") (class "Default")
      (node (ref "IC21") (pin "10") (pinfunction "O_10") (pintype "output"))
      (node (ref "IC23") (pin "12") (pinfunction "I0_12") (pintype "input"))
      (node (ref "IC41") (pin "9") (pinfunction "I0_9") (pintype "input"))
    )
    (net (code "32") (name "/SW8") (class "Default")
      (node (ref "IC21") (pin "11") (pinfunction "O_11") (pintype "output"))
      (node (ref "IC23") (pin "13") (pinfunction "I1_13") (pintype "input"))
      (node (ref "IC41") (pin "10") (pinfunction "I1_10") (pintype "input"))
    )
    (net (code "33") (name "/SW9") (class "Default")
      (node (ref "IC22") (pin "3") (pinfunction "O_3") (pintype "output"))
      (node (ref "IC24") (pin "13") (pinfunction "I1_13") (pintype "input"))
      (node (ref "IC41") (pin "11") (pinfunction "I2_11") (pintype "input"))
    )
    (net (code "34") (name "GND") (class "Default")
      (node (ref "C1") (pin "-") (pinfunction "-_-") (pintype "passive"))
      (node (ref "C10") (pin "1") (pinfunction "1_1") (pintype "passive"))
      (node (ref "C11") (pin "1") (pinfunction "1_1") (pintype "passive"))
      (node (ref "C12") (pin "1") (pinfunction "1_1") (pintype "passive"))
      (node (ref "C13") (pin "1") (pinfunction "1_1") (pintype "passive"))
      (node (ref "C14") (pin "1") (pinfunction "1_1") (pintype "passive"))
      (node (ref "C15") (pin "1") (pinfunction "1_1") (pintype "passive"))
      (node (ref "C16") (pin "1") (pinfunction "1_1") (pintype "passive"))
      (node (ref "C17") (pin "1") (pinfunction "1_1") (pintype "passive"))
      (node (ref "C18") (pin "1") (pinfunction "1_1") (pintype "passive"))
      (node (ref "C19") (pin "1") (pinfunction "1_1") (pintype "passive"))
      (node (ref "C2") (pin "-") (pinfunction "-_-") (pintype "passive"))
      (node (ref "C20") (pin "1") (pinfunction "1_1") (pintype "passive"))
      (node (ref "C21") (pin "1") (pinfunction "1_1") (pintype "passive"))
      (node (ref "C22") (pin "1") (pinfunction "1_1") (pintype "passive"))
      (node (ref "C23") (pin "1") (pinfunction "1_1") (pintype "passive"))
      (node (ref "C24") (pin "1") (pinfunction "1_1") (pintype "passive"))
      (node (ref "C25") (pin "1") (pinfunction "1_1") (pintype "passive"))
      (node (ref "C26") (pin "1") (pinfunction "1_1") (pintype "passive"))
      (node (ref "C27") (pin "1") (pinfunction "1_1") (pintype "passive"))
      (node (ref "C28") (pin "1") (pinfunction "1_1") (pintype "passive"))
      (node (ref "C29") (pin "1") (pinfunction "1_1") (pintype "passive"))
      (node (ref "C3") (pin "1") (pinfunction "1_1") (pintype "passive"))
      (node (ref "C30") (pin "1") (pinfunction "1_1") (pintype "passive"))
      (node (ref "C31") (pin "1") (pinfunction "1_1") (pintype "passive"))
      (node (ref "C32") (pin "1") (pinfunction "1_1") (pintype "passive"))
      (node (ref "C33") (pin "1") (pinfunction "1_1") (pintype "passive"))
      (node (ref "C34") (pin "1") (pinfunction "1_1") (pintype "passive"))
      (node (ref "C35") (pin "1") (pinfunction "1_1") (pintype "passive"))
      (node (ref "C36") (pin "1") (pinfunction "1_1") (pintype "passive"))
      (node (ref "C37") (pin "1") (pinfunction "1_1") (pintype "passive"))
      (node (ref "C38") (pin "1") (pinfunction "1_1") (pintype "passive"))
      (node (ref "C39") (pin "1") (pinfunction "1_1") (pintype "passive"))
      (node (ref "C4") (pin "1") (pinfunction "1_1") (pintype "passive"))
      (node (ref "C40") (pin "1") (pinfunction "1_1") (pintype "passive"))
      (node (ref "C41") (pin "1") (pinfunction "1_1") (pintype "passive"))
      (node (ref "C42") (pin "1") (pinfunction "1_1") (pintype "passive"))
      (node (ref "C43") (pin "1") (pinfunction "1_1") (pintype "passive"))
      (node (ref "C5") (pin "1") (pinfunction "1_1") (pintype "passive"))
      (node (ref "C6") (pin "1") (pinfunction "1_1") (pintype "passive"))
      (node (ref "C7") (pin "1") (pinfunction "1_1") (pintype "passive"))
      (node (ref "C8") (pin "1") (pinfunction "1_1") (pintype "passive"))
      (node (ref "C9") (pin "1") (pinfunction "1_1") (pintype "passive"))
      (node (ref "IC1") (pin "2") (pinfunction "GND_2") (pintype "passive"))
      (node (ref "IC10") (pin "6") (pinfunction "S_6") (pintype "input"))
      (node (ref "IC10") (pin "7") (pinfunction "VSS_7") (pintype "power_in"))
      (node (ref "IC10") (pin "8") (pinfunction "S_8") (pintype "input"))
      (node (ref "IC11") (pin "6") (pinfunction "S_6") (pintype "input"))
      (node (ref "IC11") (pin "7") (pinfunction "VSS_7") (pintype "power_in"))
      (node (ref "IC12") (pin "6") (pinfunction "S_6") (pintype "input"))
      (node (ref "IC12") (pin "7") (pinfunction "VSS_7") (pintype "power_in"))
      (node (ref "IC12") (pin "8") (pinfunction "S_8") (pintype "input"))
      (node (ref "IC13") (pin "6") (pinfunction "S_6") (pintype "input"))
      (node (ref "IC13") (pin "7") (pinfunction "VSS_7") (pintype "power_in"))
      (node (ref "IC14") (pin "6") (pinfunction "S_6") (pintype "input"))
      (node (ref "IC14") (pin "7") (pinfunction "VSS_7") (pintype "power_in"))
      (node (ref "IC14") (pin "8") (pinfunction "S_8") (pintype "input"))
      (node (ref "IC15") (pin "6") (pinfunction "S_6") (pintype "input"))
      (node (ref "IC15") (pin "7") (pinfunction "VSS_7") (pintype "power_in"))
      (node (ref "IC16") (pin "6") (pinfunction "S_6") (pintype "input"))
      (node (ref "IC16") (pin "7") (pinfunction "VSS_7") (pintype "power_in"))
      (node (ref "IC16") (pin "8") (pinfunction "S_8") (pintype "input"))
      (node (ref "IC17") (pin "6") (pinfunction "S_6") (pintype "input"))
      (node (ref "IC17") (pin "7") (pinfunction "VSS_7") (pintype "power_in"))
      (node (ref "IC18") (pin "6") (pinfunction "S_6") (pintype "input"))
      (node (ref "IC18") (pin "7") (pinfunction "VSS_7") (pintype "power_in"))
      (node (ref "IC18") (pin "8") (pinfunction "S_8") (pintype "input"))
      (node (ref "IC19") (pin "6") (pinfunction "S_6") (pintype "input"))
      (node (ref "IC19") (pin "7") (pinfunction "VSS_7") (pintype "power_in"))
      (node (ref "IC2") (pin "6") (pinfunction "S_6") (pintype "input"))
      (node (ref "IC2") (pin "7") (pinfunction "VSS_7") (pintype "power_in"))
      (node (ref "IC2") (pin "8") (pinfunction "S_8") (pintype "input"))
      (node (ref "IC20") (pin "7") (pinfunction "VSS_7") (pintype "power_in"))
      (node (ref "IC21") (pin "7") (pinfunction "VSS_7") (pintype "power_in"))
      (node (ref "IC22") (pin "12") (pinfunction "I0_12") (pintype "input"))
      (node (ref "IC22") (pin "13") (pinfunction "I1_13") (pintype "input"))
      (node (ref "IC22") (pin "5") (pinfunction "I0_5") (pintype "input"))
      (node (ref "IC22") (pin "6") (pinfunction "I1_6") (pintype "input"))
      (node (ref "IC22") (pin "7") (pinfunction "VSS_7") (pintype "power_in"))
      (node (ref "IC22") (pin "8") (pinfunction "I0_8") (pintype "input"))
      (node (ref "IC22") (pin "9") (pinfunction "I1_9") (pintype "input"))
      (node (ref "IC23") (pin "7") (pinfunction "VSS_7") (pintype "power_in"))
      (node (ref "IC24") (pin "7") (pinfunction "VSS_7") (pintype "power_in"))
      (node (ref "IC25") (pin "11") (pinfunction "I_11") (pintype "input"))
      (node (ref "IC25") (pin "13") (pinfunction "I_13") (pintype "input"))
      (node (ref "IC25") (pin "3") (pinfunction "I_3") (pintype "input"))
      (node (ref "IC25") (pin "5") (pinfunction "I_5") (pintype "input"))
      (node (ref "IC25") (pin "7") (pinfunction "GND_7") (pintype "power_in"))
      (node (ref "IC25") (pin "9") (pinfunction "I_9") (pintype "input"))
      (node (ref "IC26") (pin "7") (pinfunction "GND_7") (pintype "power_in"))
      (node (ref "IC27") (pin "11") (pinfunction "I_11") (pintype "input"))
      (node (ref "IC27") (pin "13") (pinfunction "I_13") (pintype "input"))
      (node (ref "IC27") (pin "7") (pinfunction "GND_7") (pintype "power_in"))
      (node (ref "IC27") (pin "9") (pinfunction "I_9") (pintype "input"))
      (node (ref "IC28") (pin "7") (pinfunction "GND_7") (pintype "power_in"))
      (node (ref "IC29") (pin "7") (pinfunction "GND_7") (pintype "power_in"))
      (node (ref "IC3") (pin "6") (pinfunction "S_6") (pintype "input"))
      (node (ref "IC3") (pin "7") (pinfunction "VSS_7") (pintype "power_in"))
      (node (ref "IC30") (pin "7") (pinfunction "GND_7") (pintype "power_in"))
      (node (ref "IC31") (pin "7") (pinfunction "GND_7") (pintype "power_in"))
      (node (ref "IC32") (pin "7") (pinfunction "GND_7") (pintype "power_in"))
      (node (ref "IC33") (pin "7") (pinfunction "GND_7") (pintype "power_in"))
      (node (ref "IC34") (pin "7") (pinfunction "GND_7") (pintype "power_in"))
      (node (ref "IC35") (pin "7") (pinfunction "GND_7") (pintype "power_in"))
      (node (ref "IC36") (pin "7") (pinfunction "GND_7") (pintype "power_in"))
      (node (ref "IC37") (pin "7") (pinfunction "GND_7") (pintype "power_in"))
      (node (ref "IC38") (pin "7") (pinfunction "GND_7") (pintype "power_in"))
      (node (ref "IC39") (pin "7") (pinfunction "GND_7") (pintype "power_in"))
      (node (ref "IC4") (pin "6") (pinfunction "S_6") (pintype "input"))
      (node (ref "IC4") (pin "7") (pinfunction "VSS_7") (pintype "power_in"))
      (node (ref "IC4") (pin "8") (pinfunction "S_8") (pintype "input"))
      (node (ref "IC40") (pin "6") (pinfunction "S_6") (pintype "input"))
      (node (ref "IC40") (pin "7") (pinfunction "VSS_7") (pintype "power_in"))
      (node (ref "IC40") (pin "8") (pinfunction "S_8") (pintype "input"))
      (node (ref "IC41") (pin "7") (pinfunction "GND_7") (pintype "power_in"))
      (node (ref "IC42") (pin "7") (pinfunction "GND_7") (pintype "power_in"))
      (node (ref "IC5") (pin "6") (pinfunction "S_6") (pintype "input"))
      (node (ref "IC5") (pin "7") (pinfunction "VSS_7") (pintype "power_in"))
      (node (ref "IC6") (pin "6") (pinfunction "S_6") (pintype "input"))
      (node (ref "IC6") (pin "7") (pinfunction "VSS_7") (pintype "power_in"))
      (node (ref "IC6") (pin "8") (pinfunction "S_8") (pintype "input"))
      (node (ref "IC7") (pin "6") (pinfunction "S_6") (pintype "input"))
      (node (ref "IC7") (pin "7") (pinfunction "VSS_7") (pintype "power_in"))
      (node (ref "IC8") (pin "6") (pinfunction "S_6") (pintype "input"))
      (node (ref "IC8") (pin "7") (pinfunction "VSS_7") (pintype "power_in"))
      (node (ref "IC8") (pin "8") (pinfunction "S_8") (pintype "input"))
      (node (ref "IC9") (pin "6") (pinfunction "S_6") (pintype "input"))
      (node (ref "IC9") (pin "7") (pinfunction "VSS_7") (pintype "power_in"))
      (node (ref "J1") (pin "1") (pinfunction "1_1") (pintype "passive"))
      (node (ref "J1") (pin "2") (pinfunction "2_2") (pintype "passive"))
      (node (ref "LED1") (pin "K") (pinfunction "C_K") (pintype "passive"))
      (node (ref "LED2") (pin "K") (pinfunction "C_K") (pintype "passive"))
      (node (ref "LED3") (pin "K") (pinfunction "C_K") (pintype "passive"))
      (node (ref "R1") (pin "1") (pinfunction "1_1") (pintype "passive"))
      (node (ref "R10") (pin "2") (pinfunction "2_2") (pintype "passive"))
      (node (ref "R2") (pin "1") (pinfunction "1_1") (pintype "passive"))
      (node (ref "R3") (pin "1") (pinfunction "1_1") (pintype "passive"))
      (node (ref "R4") (pin "1") (pinfunction "1_1") (pintype "passive"))
      (node (ref "R5") (pin "1") (pinfunction "1_1") (pintype "passive"))
      (node (ref "R6") (pin "1") (pinfunction "1_1") (pintype "passive"))
      (node (ref "R7") (pin "1") (pinfunction "1_1") (pintype "passive"))
      (node (ref "R8") (pin "1") (pinfunction "1_1") (pintype "passive"))
      (node (ref "R9") (pin "1") (pinfunction "1_1") (pintype "passive"))
    )
    (net (code "35") (name "Net-(IC2A-CLK)") (class "Default")
      (node (ref "IC2") (pin "3") (pinfunction "CLK_3") (pintype "input"))
      (node (ref "R1") (pin "2") (pinfunction "2_2") (pintype "passive"))
      (node (ref "S1") (pin "3") (pinfunction "3_3") (pintype "passive"))
      (node (ref "S1") (pin "4") (pinfunction "4_4") (pintype "passive"))
    )
    (net (code "36") (name "Net-(IC2A-Q)") (class "Default")
      (node (ref "IC2") (pin "1") (pinfunction "Q_1") (pintype "output"))
      (node (ref "IC2") (pin "11") (pinfunction "CLK_11") (pintype "input"))
      (node (ref "IC3") (pin "3") (pinfunction "CLK_3") (pintype "input"))
    )
    (net (code "37") (name "Net-(IC4A-CLK)") (class "Default")
      (node (ref "IC4") (pin "3") (pinfunction "CLK_3") (pintype "input"))
      (node (ref "R2") (pin "2") (pinfunction "2_2") (pintype "passive"))
      (node (ref "S2") (pin "3") (pinfunction "3_3") (pintype "passive"))
      (node (ref "S2") (pin "4") (pinfunction "4_4") (pintype "passive"))
    )
    (net (code "38") (name "Net-(IC4A-Q)") (class "Default")
      (node (ref "IC4") (pin "1") (pinfunction "Q_1") (pintype "output"))
      (node (ref "IC4") (pin "11") (pinfunction "CLK_11") (pintype "input"))
      (node (ref "IC5") (pin "3") (pinfunction "CLK_3") (pintype "input"))
    )
    (net (code "39") (name "Net-(IC6A-CLK)") (class "Default")
      (node (ref "IC6") (pin "3") (pinfunction "CLK_3") (pintype "input"))
      (node (ref "R3") (pin "2") (pinfunction "2_2") (pintype "passive"))
      (node (ref "S3") (pin "3") (pinfunction "3_3") (pintype "passive"))
      (node (ref "S3") (pin "4") (pinfunction "4_4") (pintype "passive"))
    )
    (net (code "40") (name "Net-(IC6A-Q)") (class "Default")
      (node (ref "IC6") (pin "1") (pinfunction "Q_1") (pintype "output"))
      (node (ref "IC6") (pin "11") (pinfunction "CLK_11") (pintype "input"))
      (node (ref "IC7") (pin "3") (pinfunction "CLK_3") (pintype "input"))
    )
    (net (code "41") (name "Net-(IC8A-CLK)") (class "Default")
      (node (ref "IC8") (pin "3") (pinfunction "CLK_3") (pintype "input"))
      (node (ref "R4") (pin "2") (pinfunction "2_2") (pintype "passive"))
      (node (ref "S4") (pin "3") (pinfunction "3_3") (pintype "passive"))
      (node (ref "S4") (pin "4") (pinfunction "4_4") (pintype "passive"))
    )
    (net (code "42") (name "Net-(IC8A-Q)") (class "Default")
      (node (ref "IC8") (pin "1") (pinfunction "Q_1") (pintype "output"))
      (node (ref "IC8") (pin "11") (pinfunction "CLK_11") (pintype "input"))
      (node (ref "IC9") (pin "3") (pinfunction "CLK_3") (pintype "input"))
    )
    (net (code "43") (name "Net-(IC10A-CLK)") (class "Default")
      (node (ref "IC10") (pin "3") (pinfunction "CLK_3") (pintype "input"))
      (node (ref "R5") (pin "2") (pinfunction "2_2") (pintype "passive"))
      (node (ref "S5") (pin "3") (pinfunction "3_3") (pintype "passive"))
      (node (ref "S5") (pin "4") (pinfunction "4_4") (pintype "passive"))
    )
    (net (code "44") (name "Net-(IC10A-Q)") (class "Default")
      (node (ref "IC10") (pin "1") (pinfunction "Q_1") (pintype "output"))
      (node (ref "IC10") (pin "11") (pinfunction "CLK_11") (pintype "input"))
      (node (ref "IC11") (pin "3") (pinfunction "CLK_3") (pintype "input"))
    )
    (net (code "45") (name "Net-(IC12A-CLK)") (class "Default")
      (node (ref "IC12") (pin "3") (pinfunction "CLK_3") (pintype "input"))
      (node (ref "R6") (pin "2") (pinfunction "2_2") (pintype "passive"))
      (node (ref "S6") (pin "3") (pinfunction "3_3") (pintype "passive"))
      (node (ref "S6") (pin "4") (pinfunction "4_4") (pintype "passive"))
    )
    (net (code "46") (name "Net-(IC12A-Q)") (class "Default")
      (node (ref "IC12") (pin "1") (pinfunction "Q_1") (pintype "output"))
      (node (ref "IC12") (pin "11") (pinfunction "CLK_11") (pintype "input"))
      (node (ref "IC13") (pin "3") (pinfunction "CLK_3") (pintype "input"))
    )
    (net (code "47") (name "Net-(IC14A-CLK)") (class "Default")
      (node (ref "IC14") (pin "3") (pinfunction "CLK_3") (pintype "input"))
      (node (ref "R7") (pin "2") (pinfunction "2_2") (pintype "passive"))
      (node (ref "S7") (pin "3") (pinfunction "3_3") (pintype "passive"))
      (node (ref "S7") (pin "4") (pinfunction "4_4") (pintype "passive"))
    )
    (net (code "48") (name "Net-(IC14A-Q)") (class "Default")
      (node (ref "IC14") (pin "1") (pinfunction "Q_1") (pintype "output"))
      (node (ref "IC14") (pin "11") (pinfunction "CLK_11") (pintype "input"))
      (node (ref "IC15") (pin "3") (pinfunction "CLK_3") (pintype "input"))
    )
    (net (code "49") (name "Net-(IC16A-CLK)") (class "Default")
      (node (ref "IC16") (pin "3") (pinfunction "CLK_3") (pintype "input"))
      (node (ref "R8") (pin "2") (pinfunction "2_2") (pintype "passive"))
      (node (ref "S8") (pin "3") (pinfunction "3_3") (pintype "passive"))
      (node (ref "S8") (pin "4") (pinfunction "4_4") (pintype "passive"))
    )
    (net (code "50") (name "Net-(IC16A-Q)") (class "Default")
      (node (ref "IC16") (pin "1") (pinfunction "Q_1") (pintype "output"))
      (node (ref "IC16") (pin "11") (pinfunction "CLK_11") (pintype "input"))
      (node (ref "IC17") (pin "3") (pinfunction "CLK_3") (pintype "input"))
    )
    (net (code "51") (name "Net-(IC18A-CLK)") (class "Default")
      (node (ref "IC18") (pin "3") (pinfunction "CLK_3") (pintype "input"))
      (node (ref "R9") (pin "2") (pinfunction "2_2") (pintype "passive"))
      (node (ref "S9") (pin "3") (pinfunction "3_3") (pintype "passive"))
      (node (ref "S9") (pin "4") (pinfunction "4_4") (pintype "passive"))
    )
    (net (code "52") (name "Net-(IC18A-Q)") (class "Default")
      (node (ref "IC18") (pin "1") (pinfunction "Q_1") (pintype "output"))
      (node (ref "IC18") (pin "11") (pinfunction "CLK_11") (pintype "input"))
      (node (ref "IC19") (pin "3") (pinfunction "CLK_3") (pintype "input"))
    )
    (net (code "53") (name "Net-(IC23A-O)") (class "Default")
      (node (ref "IC23") (pin "3") (pinfunction "O_3") (pintype "output"))
      (node (ref "IC24") (pin "1") (pinfunction "I0_1") (pintype "input"))
    )
    (net (code "54") (name "Net-(IC23B-O)") (class "Default")
      (node (ref "IC23") (pin "4") (pinfunction "O_4") (pintype "output"))
      (node (ref "IC24") (pin "2") (pinfunction "I1_2") (pintype "input"))
    )
    (net (code "55") (name "Net-(IC23C-O)") (class "Default")
      (node (ref "IC23") (pin "10") (pinfunction "O_10") (pintype "output"))
      (node (ref "IC24") (pin "5") (pinfunction "I0_5") (pintype "input"))
    )
    (net (code "56") (name "Net-(IC23D-O)") (class "Default")
      (node (ref "IC23") (pin "11") (pinfunction "O_11") (pintype "output"))
      (node (ref "IC24") (pin "6") (pinfunction "I1_6") (pintype "input"))
    )
    (net (code "57") (name "Net-(IC24A-O)") (class "Default")
      (node (ref "IC24") (pin "3") (pinfunction "O_3") (pintype "output"))
      (node (ref "IC24") (pin "8") (pinfunction "I0_8") (pintype "input"))
    )
    (net (code "58") (name "Net-(IC24B-O)") (class "Default")
      (node (ref "IC24") (pin "4") (pinfunction "O_4") (pintype "output"))
      (node (ref "IC24") (pin "9") (pinfunction "I1_9") (pintype "input"))
    )
    (net (code "59") (name "Net-(IC24C-O)") (class "Default")
      (node (ref "IC24") (pin "10") (pinfunction "O_10") (pintype "output"))
      (node (ref "IC24") (pin "12") (pinfunction "I0_12") (pintype "input"))
    )
    (net (code "60") (name "Net-(IC26A-O)") (class "Default")
      (node (ref "IC26") (pin "2") (pinfunction "O_2") (pintype "output"))
      (node (ref "LD1") (pin "CR") (pinfunction "CR_CR") (pintype "passive"))
    )
    (net (code "61") (name "Net-(IC26B-O)") (class "Default")
      (node (ref "IC26") (pin "4") (pinfunction "O_4") (pintype "output"))
      (node (ref "LD2") (pin "CR") (pinfunction "CR_CR") (pintype "passive"))
    )
    (net (code "62") (name "Net-(IC26C-O)") (class "Default")
      (node (ref "IC26") (pin "6") (pinfunction "O_6") (pintype "output"))
      (node (ref "LD3") (pin "CR") (pinfunction "CR_CR") (pintype "passive"))
    )
    (net (code "63") (name "Net-(IC26D-O)") (class "Default")
      (node (ref "IC26") (pin "8") (pinfunction "O_8") (pintype "output"))
      (node (ref "LD4") (pin "CR") (pinfunction "CR_CR") (pintype "passive"))
    )
    (net (code "64") (name "Net-(IC26E-O)") (class "Default")
      (node (ref "IC26") (pin "10") (pinfunction "O_10") (pintype "output"))
      (node (ref "LD5") (pin "CR") (pinfunction "CR_CR") (pintype "passive"))
    )
    (net (code "65") (name "Net-(IC26F-O)") (class "Default")
      (node (ref "IC26") (pin "12") (pinfunction "O_12") (pintype "output"))
      (node (ref "LD6") (pin "CR") (pinfunction "CR_CR") (pintype "passive"))
    )
    (net (code "66") (name "Net-(IC27A-O)") (class "Default")
      (node (ref "IC27") (pin "2") (pinfunction "O_2") (pintype "output"))
      (node (ref "LD7") (pin "CR") (pinfunction "CR_CR") (pintype "passive"))
    )
    (net (code "67") (name "Net-(IC27B-O)") (class "Default")
      (node (ref "IC27") (pin "4") (pinfunction "O_4") (pintype "output"))
      (node (ref "LD8") (pin "CR") (pinfunction "CR_CR") (pintype "passive"))
    )
    (net (code "68") (name "Net-(IC27C-O)") (class "Default")
      (node (ref "IC27") (pin "6") (pinfunction "O_6") (pintype "output"))
      (node (ref "LD9") (pin "CR") (pinfunction "CR_CR") (pintype "passive"))
    )
    (net (code "69") (name "Net-(IC28A-O)") (class "Default")
      (node (ref "IC28") (pin "2") (pinfunction "O_2") (pintype "output"))
      (node (ref "LD1") (pin "CX") (pinfunction "CG_CX") (pintype "passive"))
    )
    (net (code "70") (name "Net-(IC28B-O)") (class "Default")
      (node (ref "IC28") (pin "4") (pinfunction "O_4") (pintype "output"))
      (node (ref "LD2") (pin "CX") (pinfunction "CG_CX") (pintype "passive"))
    )
    (net (code "71") (name "Net-(IC28C-O)") (class "Default")
      (node (ref "IC28") (pin "6") (pinfunction "O_6") (pintype "output"))
      (node (ref "LD3") (pin "CX") (pinfunction "CG_CX") (pintype "passive"))
    )
    (net (code "72") (name "Net-(IC28D-O)") (class "Default")
      (node (ref "IC28") (pin "8") (pinfunction "O_8") (pintype "output"))
      (node (ref "LD4") (pin "CX") (pinfunction "CG_CX") (pintype "passive"))
    )
    (net (code "73") (name "Net-(IC28E-O)") (class "Default")
      (node (ref "IC28") (pin "10") (pinfunction "O_10") (pintype "output"))
      (node (ref "LD5") (pin "CX") (pinfunction "CG_CX") (pintype "passive"))
    )
    (net (code "74") (name "Net-(IC28F-O)") (class "Default")
      (node (ref "IC28") (pin "12") (pinfunction "O_12") (pintype "output"))
      (node (ref "LD6") (pin "CX") (pinfunction "CG_CX") (pintype "passive"))
    )
    (net (code "75") (name "Net-(IC29A-O)") (class "Default")
      (node (ref "IC29") (pin "2") (pinfunction "O_2") (pintype "output"))
      (node (ref "LD7") (pin "CX") (pinfunction "CG_CX") (pintype "passive"))
    )
    (net (code "76") (name "Net-(IC29B-O)") (class "Default")
      (node (ref "IC29") (pin "4") (pinfunction "O_4") (pintype "output"))
      (node (ref "LD8") (pin "CX") (pinfunction "CG_CX") (pintype "passive"))
    )
    (net (code "77") (name "Net-(IC29C-O)") (class "Default")
      (node (ref "IC29") (pin "6") (pinfunction "O_6") (pintype "output"))
      (node (ref "LD9") (pin "CX") (pinfunction "CG_CX") (pintype "passive"))
    )
    (net (code "78") (name "Net-(IC30A-O)") (class "Default")
      (node (ref "IC30") (pin "12") (pinfunction "O_12") (pintype "output"))
      (node (ref "IC33") (pin "1") (pinfunction "I0_1") (pintype "input"))
    )
    (net (code "79") (name "Net-(IC30B-O)") (class "Default")
      (node (ref "IC30") (pin "6") (pinfunction "O_6") (pintype "output"))
      (node (ref "IC33") (pin "4") (pinfunction "I0_4") (pintype "input"))
    )
    (net (code "80") (name "Net-(IC30C-O)") (class "Default")
      (node (ref "IC30") (pin "8") (pinfunction "O_8") (pintype "output"))
      (node (ref "IC33") (pin "9") (pinfunction "I0_9") (pintype "input"))
    )
    (net (code "81") (name "Net-(IC31A-O)") (class "Default")
      (node (ref "IC31") (pin "12") (pinfunction "O_12") (pintype "output"))
      (node (ref "IC33") (pin "2") (pinfunction "I1_2") (pintype "input"))
    )
    (net (code "82") (name "Net-(IC31B-O)") (class "Default")
      (node (ref "IC31") (pin "6") (pinfunction "O_6") (pintype "output"))
      (node (ref "IC33") (pin "5") (pinfunction "I1_5") (pintype "input"))
    )
    (net (code "83") (name "Net-(IC31C-O)") (class "Default")
      (node (ref "IC31") (pin "8") (pinfunction "O_8") (pintype "output"))
      (node (ref "IC33") (pin "10") (pinfunction "I1_10") (pintype "input"))
    )
    (net (code "84") (name "Net-(IC32A-O)") (class "Default")
      (node (ref "IC32") (pin "12") (pinfunction "O_12") (pintype "output"))
      (node (ref "IC33") (pin "12") (pinfunction "I0_12") (pintype "input"))
    )
    (net (code "85") (name "Net-(IC32B-O)") (class "Default")
      (node (ref "IC32") (pin "6") (pinfunction "O_6") (pintype "output"))
      (node (ref "IC33") (pin "13") (pinfunction "I1_13") (pintype "input"))
    )
    (net (code "86") (name "Net-(IC33A-O)") (class "Default")
      (node (ref "IC33") (pin "3") (pinfunction "O_3") (pintype "output"))
      (node (ref "IC34") (pin "1") (pinfunction "I0_1") (pintype "input"))
    )
    (net (code "87") (name "Net-(IC33B-O)") (class "Default")
      (node (ref "IC33") (pin "6") (pinfunction "O_6") (pintype "output"))
      (node (ref "IC34") (pin "2") (pinfunction "I1_2") (pintype "input"))
    )
    (net (code "88") (name "Net-(IC33C-O)") (class "Default")
      (node (ref "IC33") (pin "8") (pinfunction "O_8") (pintype "output"))
      (node (ref "IC34") (pin "4") (pinfunction "I0_4") (pintype "input"))
    )
    (net (code "89") (name "Net-(IC33D-O)") (class "Default")
      (node (ref "IC33") (pin "11") (pinfunction "O_11") (pintype "output"))
      (node (ref "IC34") (pin "5") (pinfunction "I1_5") (pintype "input"))
    )
    (net (code "90") (name "Net-(IC34A-O)") (class "Default")
      (node (ref "IC34") (pin "3") (pinfunction "O_3") (pintype "output"))
      (node (ref "IC34") (pin "9") (pinfunction "I0_9") (pintype "input"))
    )
    (net (code "91") (name "Net-(IC34B-O)") (class "Default")
      (node (ref "IC34") (pin "10") (pinfunction "I1_10") (pintype "input"))
      (node (ref "IC34") (pin "6") (pinfunction "O_6") (pintype "output"))
    )
    (net (code "92") (name "Net-(IC35A-O)") (class "Default")
      (node (ref "IC35") (pin "12") (pinfunction "O_12") (pintype "output"))
      (node (ref "IC38") (pin "1") (pinfunction "I0_1") (pintype "input"))
    )
    (net (code "93") (name "Net-(IC35B-O)") (class "Default")
      (node (ref "IC35") (pin "6") (pinfunction "O_6") (pintype "output"))
      (node (ref "IC38") (pin "4") (pinfunction "I0_4") (pintype "input"))
    )
    (net (code "94") (name "Net-(IC35C-O)") (class "Default")
      (node (ref "IC35") (pin "8") (pinfunction "O_8") (pintype "output"))
      (node (ref "IC38") (pin "9") (pinfunction "I0_9") (pintype "input"))
    )
    (net (code "95") (name "Net-(IC36A-O)") (class "Default")
      (node (ref "IC36") (pin "12") (pinfunction "O_12") (pintype "output"))
      (node (ref "IC38") (pin "2") (pinfunction "I1_2") (pintype "input"))
    )
    (net (code "96") (name "Net-(IC36B-O)") (class "Default")
      (node (ref "IC36") (pin "6") (pinfunction "O_6") (pintype "output"))
      (node (ref "IC38") (pin "5") (pinfunction "I1_5") (pintype "input"))
    )
    (net (code "97") (name "Net-(IC36C-O)") (class "Default")
      (node (ref "IC36") (pin "8") (pinfunction "O_8") (pintype "output"))
      (node (ref "IC38") (pin "10") (pinfunction "I1_10") (pintype "input"))
    )
    (net (code "98") (name "Net-(IC37A-O)") (class "Default")
      (node (ref "IC37") (pin "12") (pinfunction "O_12") (pintype "output"))
      (node (ref "IC38") (pin "12") (pinfunction "I0_12") (pintype "input"))
    )
    (net (code "99") (name "Net-(IC37B-O)") (class "Default")
      (node (ref "IC37") (pin "6") (pinfunction "O_6") (pintype "output"))
      (node (ref "IC38") (pin "13") (pinfunction "I1_13") (pintype "input"))
    )
    (net (code "100") (name "Net-(IC38A-O)") (class "Default")
      (node (ref "IC38") (pin "3") (pinfunction "O_3") (pintype "output"))
      (node (ref "IC39") (pin "1") (pinfunction "I0_1") (pintype "input"))
    )
    (net (code "101") (name "Net-(IC38B-O)") (class "Default")
      (node (ref "IC38") (pin "6") (pinfunction "O_6") (pintype "output"))
      (node (ref "IC39") (pin "2") (pinfunction "I1_2") (pintype "input"))
    )
    (net (code "102") (name "Net-(IC38C-O)") (class "Default")
      (node (ref "IC38") (pin "8") (pinfunction "O_8") (pintype "output"))
      (node (ref "IC39") (pin "4") (pinfunction "I0_4") (pintype "input"))
    )
    (net (code "103") (name "Net-(IC38D-O)") (class "Default")
      (node (ref "IC38") (pin "11") (pinfunction "O_11") (pintype "output"))
      (node (ref "IC39") (pin "5") (pinfunction "I1_5") (pintype "input"))
    )
    (net (code "104") (name "Net-(IC39A-O)") (class "Default")
      (node (ref "IC39") (pin "3") (pinfunction "O_3") (pintype "output"))
      (node (ref "IC39") (pin "9") (pinfunction "I0_9") (pintype "input"))
    )
    (net (code "105") (name "Net-(IC39B-O)") (class "Default")
      (node (ref "IC39") (pin "10") (pinfunction "I1_10") (pintype "input"))
      (node (ref "IC39") (pin "6") (pinfunction "O_6") (pintype "output"))
    )
    (net (code "106") (name "Net-(IC40A-D)") (class "Default")
      (node (ref "IC40") (pin "12") (pinfunction "~{Q}_12") (pintype "output"))
      (node (ref "IC40") (pin "5") (pinfunction "D_5") (pintype "input"))
    )
    (net (code "107") (name "Net-(IC40A-Q)") (class "Default")
      (node (ref "IC40") (pin "1") (pinfunction "Q_1") (pintype "output"))
      (node (ref "LED1") (pin "A") (pinfunction "A_A") (pintype "passive"))
    )
    (net (code "108") (name "Net-(IC40A-~{Q})") (class "Default")
      (node (ref "IC40") (pin "2") (pinfunction "~{Q}_2") (pintype "output"))
      (node (ref "IC40") (pin "9") (pinfunction "D_9") (pintype "input"))
    )
    (net (code "109") (name "Net-(IC40B-Q)") (class "Default")
      (node (ref "IC40") (pin "13") (pinfunction "Q_13") (pintype "output"))
      (node (ref "LED2") (pin "A") (pinfunction "A_A") (pintype "passive"))
    )
    (net (code "110") (name "Net-(IC41A-O)") (class "Default")
      (node (ref "IC41") (pin "12") (pinfunction "O_12") (pintype "output"))
      (node (ref "IC42") (pin "1") (pinfunction "I0_1") (pintype "input"))
    )
    (net (code "111") (name "Net-(IC41B-O)") (class "Default")
      (node (ref "IC41") (pin "6") (pinfunction "O_6") (pintype "output"))
      (node (ref "IC42") (pin "2") (pinfunction "I1_2") (pintype "input"))
    )
    (net (code "112") (name "Net-(IC41C-O)") (class "Default")
      (node (ref "IC41") (pin "8") (pinfunction "O_8") (pintype "output"))
      (node (ref "IC42") (pin "13") (pinfunction "I2_13") (pintype "input"))
    )
    (net (code "113") (name "Net-(IC42A-O)") (class "Default")
      (node (ref "IC42") (pin "12") (pinfunction "O_12") (pintype "output"))
      (node (ref "LED3") (pin "A") (pinfunction "A_A") (pintype "passive"))
    )
    (net (code "114") (name "VCC") (class "Default")
      (node (ref "C10") (pin "2") (pinfunction "2_2") (pintype "passive"))
      (node (ref "C11") (pin "2") (pinfunction "2_2") (pintype "passive"))
      (node (ref "C12") (pin "2") (pinfunction "2_2") (pintype "passive"))
      (node (ref "C13") (pin "2") (pinfunction "2_2") (pintype "passive"))
      (node (ref "C14") (pin "2") (pinfunction "2_2") (pintype "passive"))
      (node (ref "C15") (pin "2") (pinfunction "2_2") (pintype "passive"))
      (node (ref "C16") (pin "2") (pinfunction "2_2") (pintype "passive"))
      (node (ref "C17") (pin "2") (pinfunction "2_2") (pintype "passive"))
      (node (ref "C18") (pin "2") (pinfunction "2_2") (pintype "passive"))
      (node (ref "C19") (pin "2") (pinfunction "2_2") (pintype "passive"))
      (node (ref "C2") (pin "+") (pinfunction "+_+") (pintype "passive"))
      (node (ref "C20") (pin "2") (pinfunction "2_2") (pintype "passive"))
      (node (ref "C21") (pin "2") (pinfunction "2_2") (pintype "passive"))
      (node (ref "C22") (pin "2") (pinfunction "2_2") (pintype "passive"))
      (node (ref "C23") (pin "2") (pinfunction "2_2") (pintype "passive"))
      (node (ref "C24") (pin "2") (pinfunction "2_2") (pintype "passive"))
      (node (ref "C25") (pin "2") (pinfunction "2_2") (pintype "passive"))
      (node (ref "C26") (pin "2") (pinfunction "2_2") (pintype "passive"))
      (node (ref "C27") (pin "2") (pinfunction "2_2") (pintype "passive"))
      (node (ref "C28") (pin "2") (pinfunction "2_2") (pintype "passive"))
      (node (ref "C29") (pin "2") (pinfunction "2_2") (pintype "passive"))
      (node (ref "C3") (pin "2") (pinfunction "2_2") (pintype "passive"))
      (node (ref "C30") (pin "2") (pinfunction "2_2") (pintype "passive"))
      (node (ref "C31") (pin "2") (pinfunction "2_2") (pintype "passive"))
      (node (ref "C32") (pin "2") (pinfunction "2_2") (pintype "passive"))
      (node (ref "C33") (pin "2") (pinfunction "2_2") (pintype "passive"))
      (node (ref "C34") (pin "2") (pinfunction "2_2") (pintype "passive"))
      (node (ref "C35") (pin "2") (pinfunction "2_2") (pintype "passive"))
      (node (ref "C36") (pin "2") (pinfunction "2_2") (pintype "passive"))
      (node (ref "C37") (pin "2") (pinfunction "2_2") (pintype "passive"))
      (node (ref "C38") (pin "2") (pinfunction "2_2") (pintype "passive"))
      (node (ref "C39") (pin "2") (pinfunction "2_2") (pintype "passive"))
      (node (ref "C4") (pin "2") (pinfunction "2_2") (pintype "passive"))
      (node (ref "C40") (pin "2") (pinfunction "2_2") (pintype "passive"))
      (node (ref "C41") (pin "2") (pinfunction "2_2") (pintype "passive"))
      (node (ref "C42") (pin "2") (pinfunction "2_2") (pintype "passive"))
      (node (ref "C43") (pin "2") (pinfunction "2_2") (pintype "passive"))
      (node (ref "C5") (pin "2") (pinfunction "2_2") (pintype "passive"))
      (node (ref "C6") (pin "2") (pinfunction "2_2") (pintype "passive"))
      (node (ref "C7") (pin "2") (pinfunction "2_2") (pintype "passive"))
      (node (ref "C8") (pin "2") (pinfunction "2_2") (pintype "passive"))
      (node (ref "C9") (pin "2") (pinfunction "2_2") (pintype "passive"))
      (node (ref "IC1") (pin "3") (pinfunction "VO_3") (pintype "passive"))
      (node (ref "IC10") (pin "14") (pinfunction "VDD_14") (pintype "power_in"))
      (node (ref "IC10") (pin "5") (pinfunction "D_5") (pintype "input"))
      (node (ref "IC11") (pin "14") (pinfunction "VDD_14") (pintype "power_in"))
      (node (ref "IC12") (pin "14") (pinfunction "VDD_14") (pintype "power_in"))
      (node (ref "IC12") (pin "5") (pinfunction "D_5") (pintype "input"))
      (node (ref "IC13") (pin "14") (pinfunction "VDD_14") (pintype "power_in"))
      (node (ref "IC14") (pin "14") (pinfunction "VDD_14") (pintype "power_in"))
      (node (ref "IC14") (pin "5") (pinfunction "D_5") (pintype "input"))
      (node (ref "IC15") (pin "14") (pinfunction "VDD_14") (pintype "power_in"))
      (node (ref "IC16") (pin "14") (pinfunction "VDD_14") (pintype "power_in"))
      (node (ref "IC16") (pin "5") (pinfunction "D_5") (pintype "input"))
      (node (ref "IC17") (pin "14") (pinfunction "VDD_14") (pintype "power_in"))
      (node (ref "IC18") (pin "14") (pinfunction "VDD_14") (pintype "power_in"))
      (node (ref "IC18") (pin "5") (pinfunction "D_5") (pintype "input"))
      (node (ref "IC19") (pin "14") (pinfunction "VDD_14") (pintype "power_in"))
      (node (ref "IC2") (pin "14") (pinfunction "VDD_14") (pintype "power_in"))
      (node (ref "IC2") (pin "5") (pinfunction "D_5") (pintype "input"))
      (node (ref "IC20") (pin "14") (pinfunction "VDD_14") (pintype "power_in"))
      (node (ref "IC21") (pin "14") (pinfunction "VDD_14") (pintype "power_in"))
      (node (ref "IC22") (pin "14") (pinfunction "VDD_14") (pintype "power_in"))
      (node (ref "IC23") (pin "14") (pinfunction "VDD_14") (pintype "power_in"))
      (node (ref "IC24") (pin "14") (pinfunction "VDD_14") (pintype "power_in"))
      (node (ref "IC25") (pin "14") (pinfunction "VCC_14") (pintype "power_in"))
      (node (ref "IC26") (pin "14") (pinfunction "VCC_14") (pintype "power_in"))
      (node (ref "IC27") (pin "14") (pinfunction "VCC_14") (pintype "power_in"))
      (node (ref "IC28") (pin "14") (pinfunction "VCC_14") (pintype "power_in"))
      (node (ref "IC29") (pin "14") (pinfunction "VCC_14") (pintype "power_in"))
      (node (ref "IC3") (pin "14") (pinfunction "VDD_14") (pintype "power_in"))
      (node (ref "IC30") (pin "14") (pinfunction "VCC_14") (pintype "power_in"))
      (node (ref "IC31") (pin "14") (pinfunction "VCC_14") (pintype "power_in"))
      (node (ref "IC32") (pin "14") (pinfunction "VCC_14") (pintype "power_in"))
      (node (ref "IC33") (pin "14") (pinfunction "VCC_14") (pintype "power_in"))
      (node (ref "IC34") (pin "14") (pinfunction "VCC_14") (pintype "power_in"))
      (node (ref "IC35") (pin "14") (pinfunction "VCC_14") (pintype "power_in"))
      (node (ref "IC36") (pin "14") (pinfunction "VCC_14") (pintype "power_in"))
      (node (ref "IC37") (pin "14") (pinfunction "VCC_14") (pintype "power_in"))
      (node (ref "IC38") (pin "14") (pinfunction "VCC_14") (pintype "power_in"))
      (node (ref "IC39") (pin "14") (pinfunction "VCC_14") (pintype "power_in"))
      (node (ref "IC4") (pin "14") (pinfunction "VDD_14") (pintype "power_in"))
      (node (ref "IC4") (pin "5") (pinfunction "D_5") (pintype "input"))
      (node (ref "IC40") (pin "14") (pinfunction "VDD_14") (pintype "power_in"))
      (node (ref "IC41") (pin "14") (pinfunction "VCC_14") (pintype "power_in"))
      (node (ref "IC42") (pin "14") (pinfunction "VCC_14") (pintype "power_in"))
      (node (ref "IC5") (pin "14") (pinfunction "VDD_14") (pintype "power_in"))
      (node (ref "IC6") (pin "14") (pinfunction "VDD_14") (pintype "power_in"))
      (node (ref "IC6") (pin "5") (pinfunction "D_5") (pintype "input"))
      (node (ref "IC7") (pin "14") (pinfunction "VDD_14") (pintype "power_in"))
      (node (ref "IC8") (pin "14") (pinfunction "VDD_14") (pintype "power_in"))
      (node (ref "IC8") (pin "5") (pinfunction "D_5") (pintype "input"))
      (node (ref "IC9") (pin "14") (pinfunction "VDD_14") (pintype "power_in"))
      (node (ref "LD1") (pin "A") (pinfunction "A_A") (pintype "passive"))
      (node (ref "LD2") (pin "A") (pinfunction "A_A") (pintype "passive"))
      (node (ref "LD3") (pin "A") (pinfunction "A_A") (pintype "passive"))
      (node (ref "LD4") (pin "A") (pinfunction "A_A") (pintype "passive"))
      (node (ref "LD5") (pin "A") (pinfunction "A_A") (pintype "passive"))
      (node (ref "LD6") (pin "A") (pinfunction "A_A") (pintype "passive"))
      (node (ref "LD7") (pin "A") (pinfunction "A_A") (pintype "passive"))
      (node (ref "LD8") (pin "A") (pinfunction "A_A") (pintype "passive"))
      (node (ref "LD9") (pin "A") (pinfunction "A_A") (pintype "passive"))
      (node (ref "S1") (pin "1") (pinfunction "1_1") (pintype "passive"))
      (node (ref "S1") (pin "2") (pinfunction "2_2") (pintype "passive"))
      (node (ref "S10") (pin "1") (pinfunction "1_1") (pintype "passive"))
      (node (ref "S10") (pin "2") (pinfunction "2_2") (pintype "passive"))
      (node (ref "S2") (pin "1") (pinfunction "1_1") (pintype "passive"))
      (node (ref "S2") (pin "2") (pinfunction "2_2") (pintype "passive"))
      (node (ref "S3") (pin "1") (pinfunction "1_1") (pintype "passive"))
      (node (ref "S3") (pin "2") (pinfunction "2_2") (pintype "passive"))
      (node (ref "S4") (pin "1") (pinfunction "1_1") (pintype "passive"))
      (node (ref "S4") (pin "2") (pinfunction "2_2") (pintype "passive"))
      (node (ref "S5") (pin "1") (pinfunction "1_1") (pintype "passive"))
      (node (ref "S5") (pin "2") (pinfunction "2_2") (pintype "passive"))
      (node (ref "S6") (pin "1") (pinfunction "1_1") (pintype "passive"))
      (node (ref "S6") (pin "2") (pinfunction "2_2") (pintype "passive"))
      (node (ref "S7") (pin "1") (pinfunction "1_1") (pintype "passive"))
      (node (ref "S7") (pin "2") (pinfunction "2_2") (pintype "passive"))
      (node (ref "S8") (pin "1") (pinfunction "1_1") (pintype "passive"))
      (node (ref "S8") (pin "2") (pinfunction "2_2") (pintype "passive"))
      (node (ref "S9") (pin "1") (pinfunction "1_1") (pintype "passive"))
      (node (ref "S9") (pin "2") (pinfunction "2_2") (pintype "passive"))
    )
    (net (code "115") (name "unconnected-(IC2A-~{Q}-Pad2)") (class "Default")
      (node (ref "IC2") (pin "2") (pinfunction "~{Q}_2") (pintype "output"))
    )
    (net (code "116") (name "unconnected-(IC2B-~{Q}-Pad12)") (class "Default")
      (node (ref "IC2") (pin "12") (pinfunction "~{Q}_12") (pintype "output"))
    )
    (net (code "117") (name "unconnected-(IC3A-~{Q}-Pad2)") (class "Default")
      (node (ref "IC3") (pin "2") (pinfunction "~{Q}_2") (pintype "output"))
    )
    (net (code "118") (name "unconnected-(IC4A-~{Q}-Pad2)") (class "Default")
      (node (ref "IC4") (pin "2") (pinfunction "~{Q}_2") (pintype "output"))
    )
    (net (code "119") (name "unconnected-(IC4B-~{Q}-Pad12)") (class "Default")
      (node (ref "IC4") (pin "12") (pinfunction "~{Q}_12") (pintype "output"))
    )
    (net (code "120") (name "unconnected-(IC5A-~{Q}-Pad2)") (class "Default")
      (node (ref "IC5") (pin "2") (pinfunction "~{Q}_2") (pintype "output"))
    )
    (net (code "121") (name "unconnected-(IC6A-~{Q}-Pad2)") (class "Default")
      (node (ref "IC6") (pin "2") (pinfunction "~{Q}_2") (pintype "output"))
    )
    (net (code "122") (name "unconnected-(IC6B-~{Q}-Pad12)") (class "Default")
      (node (ref "IC6") (pin "12") (pinfunction "~{Q}_12") (pintype "output"))
    )
    (net (code "123") (name "unconnected-(IC7A-~{Q}-Pad2)") (class "Default")
      (node (ref "IC7") (pin "2") (pinfunction "~{Q}_2") (pintype "output"))
    )
    (net (code "124") (name "unconnected-(IC8A-~{Q}-Pad2)") (class "Default")
      (node (ref "IC8") (pin "2") (pinfunction "~{Q}_2") (pintype "output"))
    )
    (net (code "125") (name "unconnected-(IC8B-~{Q}-Pad12)") (class "Default")
      (node (ref "IC8") (pin "12") (pinfunction "~{Q}_12") (pintype "output"))
    )
    (net (code "126") (name "unconnected-(IC9A-~{Q}-Pad2)") (class "Default")
      (node (ref "IC9") (pin "2") (pinfunction "~{Q}_2") (pintype "output"))
    )
    (net (code "127") (name "unconnected-(IC10A-~{Q}-Pad2)") (class "Default")
      (node (ref "IC10") (pin "2") (pinfunction "~{Q}_2") (pintype "output"))
    )
    (net (code "128") (name "unconnected-(IC10B-~{Q}-Pad12)") (class "Default")
      (node (ref "IC10") (pin "12") (pinfunction "~{Q}_12") (pintype "output"))
    )
    (net (code "129") (name "unconnected-(IC11A-~{Q}-Pad2)") (class "Default")
      (node (ref "IC11") (pin "2") (pinfunction "~{Q}_2") (pintype "output"))
    )
    (net (code "130") (name "unconnected-(IC12A-~{Q}-Pad2)") (class "Default")
      (node (ref "IC12") (pin "2") (pinfunction "~{Q}_2") (pintype "output"))
    )
    (net (code "131") (name "unconnected-(IC12B-~{Q}-Pad12)") (class "Default")
      (node (ref "IC12") (pin "12") (pinfunction "~{Q}_12") (pintype "output"))
    )
    (net (code "132") (name "unconnected-(IC13A-~{Q}-Pad2)") (class "Default")
      (node (ref "IC13") (pin "2") (pinfunction "~{Q}_2") (pintype "output"))
    )
    (net (code "133") (name "unconnected-(IC14A-~{Q}-Pad2)") (class "Default")
      (node (ref "IC14") (pin "2") (pinfunction "~{Q}_2") (pintype "output"))
    )
    (net (code "134") (name "unconnected-(IC14B-~{Q}-Pad12)") (class "Default")
      (node (ref "IC14") (pin "12") (pinfunction "~{Q}_12") (pintype "output"))
    )
    (net (code "135") (name "unconnected-(IC15A-~{Q}-Pad2)") (class "Default")
      (node (ref "IC15") (pin "2") (pinfunction "~{Q}_2") (pintype "output"))
    )
    (net (code "136") (name "unconnected-(IC16A-~{Q}-Pad2)") (class "Default")
      (node (ref "IC16") (pin "2") (pinfunction "~{Q}_2") (pintype "output"))
    )
    (net (code "137") (name "unconnected-(IC16B-~{Q}-Pad12)") (class "Default")
      (node (ref "IC16") (pin "12") (pinfunction "~{Q}_12") (pintype "output"))
    )
    (net (code "138") (name "unconnected-(IC17A-~{Q}-Pad2)") (class "Default")
      (node (ref "IC17") (pin "2") (pinfunction "~{Q}_2") (pintype "output"))
    )
    (net (code "139") (name "unconnected-(IC18A-~{Q}-Pad2)") (class "Default")
      (node (ref "IC18") (pin "2") (pinfunction "~{Q}_2") (pintype "output"))
    )
    (net (code "140") (name "unconnected-(IC18B-~{Q}-Pad12)") (class "Default")
      (node (ref "IC18") (pin "12") (pinfunction "~{Q}_12") (pintype "output"))
    )
    (net (code "141") (name "unconnected-(IC19A-~{Q}-Pad2)") (class "Default")
      (node (ref "IC19") (pin "2") (pinfunction "~{Q}_2") (pintype "output"))
    )
    (net (code "142") (name "unconnected-(IC22B-O-Pad4)") (class "Default")
      (node (ref "IC22") (pin "4") (pinfunction "O_4") (pintype "output"))
    )
    (net (code "143") (name "unconnected-(IC22C-O-Pad10)") (class "Default")
      (node (ref "IC22") (pin "10") (pinfunction "O_10") (pintype "output"))
    )
    (net (code "144") (name "unconnected-(IC22D-O-Pad11)") (class "Default")
      (node (ref "IC22") (pin "11") (pinfunction "O_11") (pintype "output"))
    )
    (net (code "145") (name "unconnected-(IC25B-O-Pad4)") (class "Default")
      (node (ref "IC25") (pin "4") (pinfunction "O_4") (pintype "output"))
    )
    (net (code "146") (name "unconnected-(IC25C-O-Pad6)") (class "Default")
      (node (ref "IC25") (pin "6") (pinfunction "O_6") (pintype "output"))
    )
    (net (code "147") (name "unconnected-(IC25D-O-Pad8)") (class "Default")
      (node (ref "IC25") (pin "8") (pinfunction "O_8") (pintype "output"))
    )
    (net (code "148") (name "unconnected-(IC25E-O-Pad10)") (class "Default")
      (node (ref "IC25") (pin "10") (pinfunction "O_10") (pintype "output"))
    )
    (net (code "149") (name "unconnected-(IC25F-O-Pad12)") (class "Default")
      (node (ref "IC25") (pin "12") (pinfunction "O_12") (pintype "output"))
    )
    (net (code "150") (name "unconnected-(IC27D-O-Pad8)") (class "Default")
      (node (ref "IC27") (pin "8") (pinfunction "O_8") (pintype "output"))
    )
    (net (code "151") (name "unconnected-(IC27E-O-Pad10)") (class "Default")
      (node (ref "IC27") (pin "10") (pinfunction "O_10") (pintype "output"))
    )
    (net (code "152") (name "unconnected-(IC27F-O-Pad12)") (class "Default")
      (node (ref "IC27") (pin "12") (pinfunction "O_12") (pintype "output"))
    )
  )
)
